# 7inch.net
KiCad netlist of a schematic drawn in Altium Designer
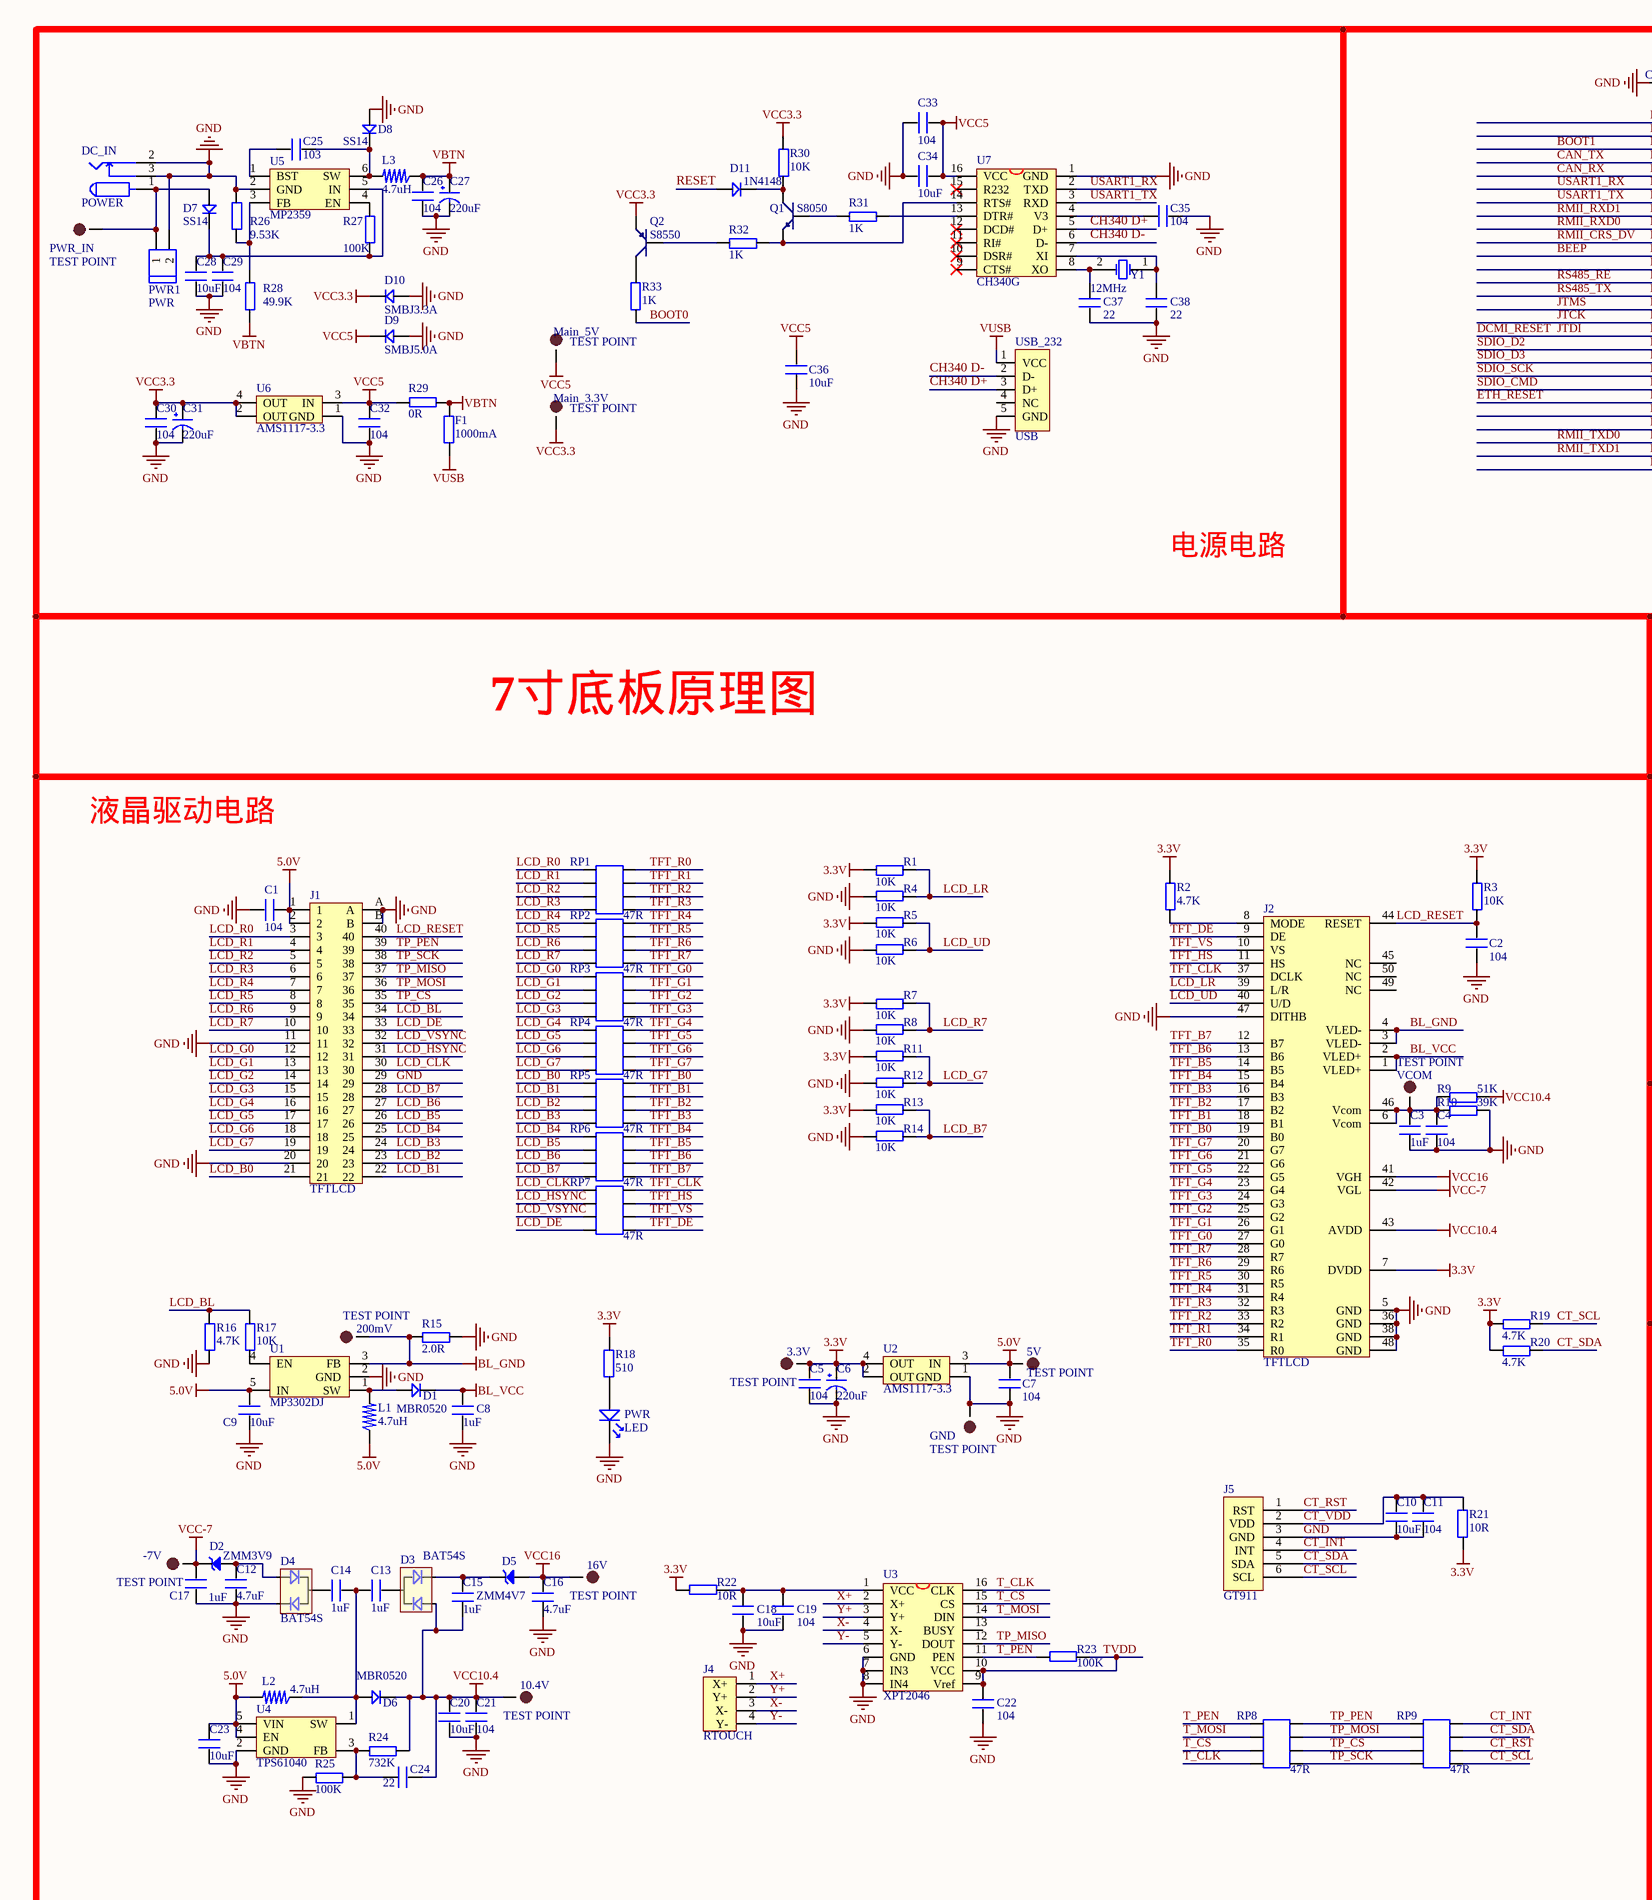
[diagram p0: 7inch底板原理图.SchDoc, left]
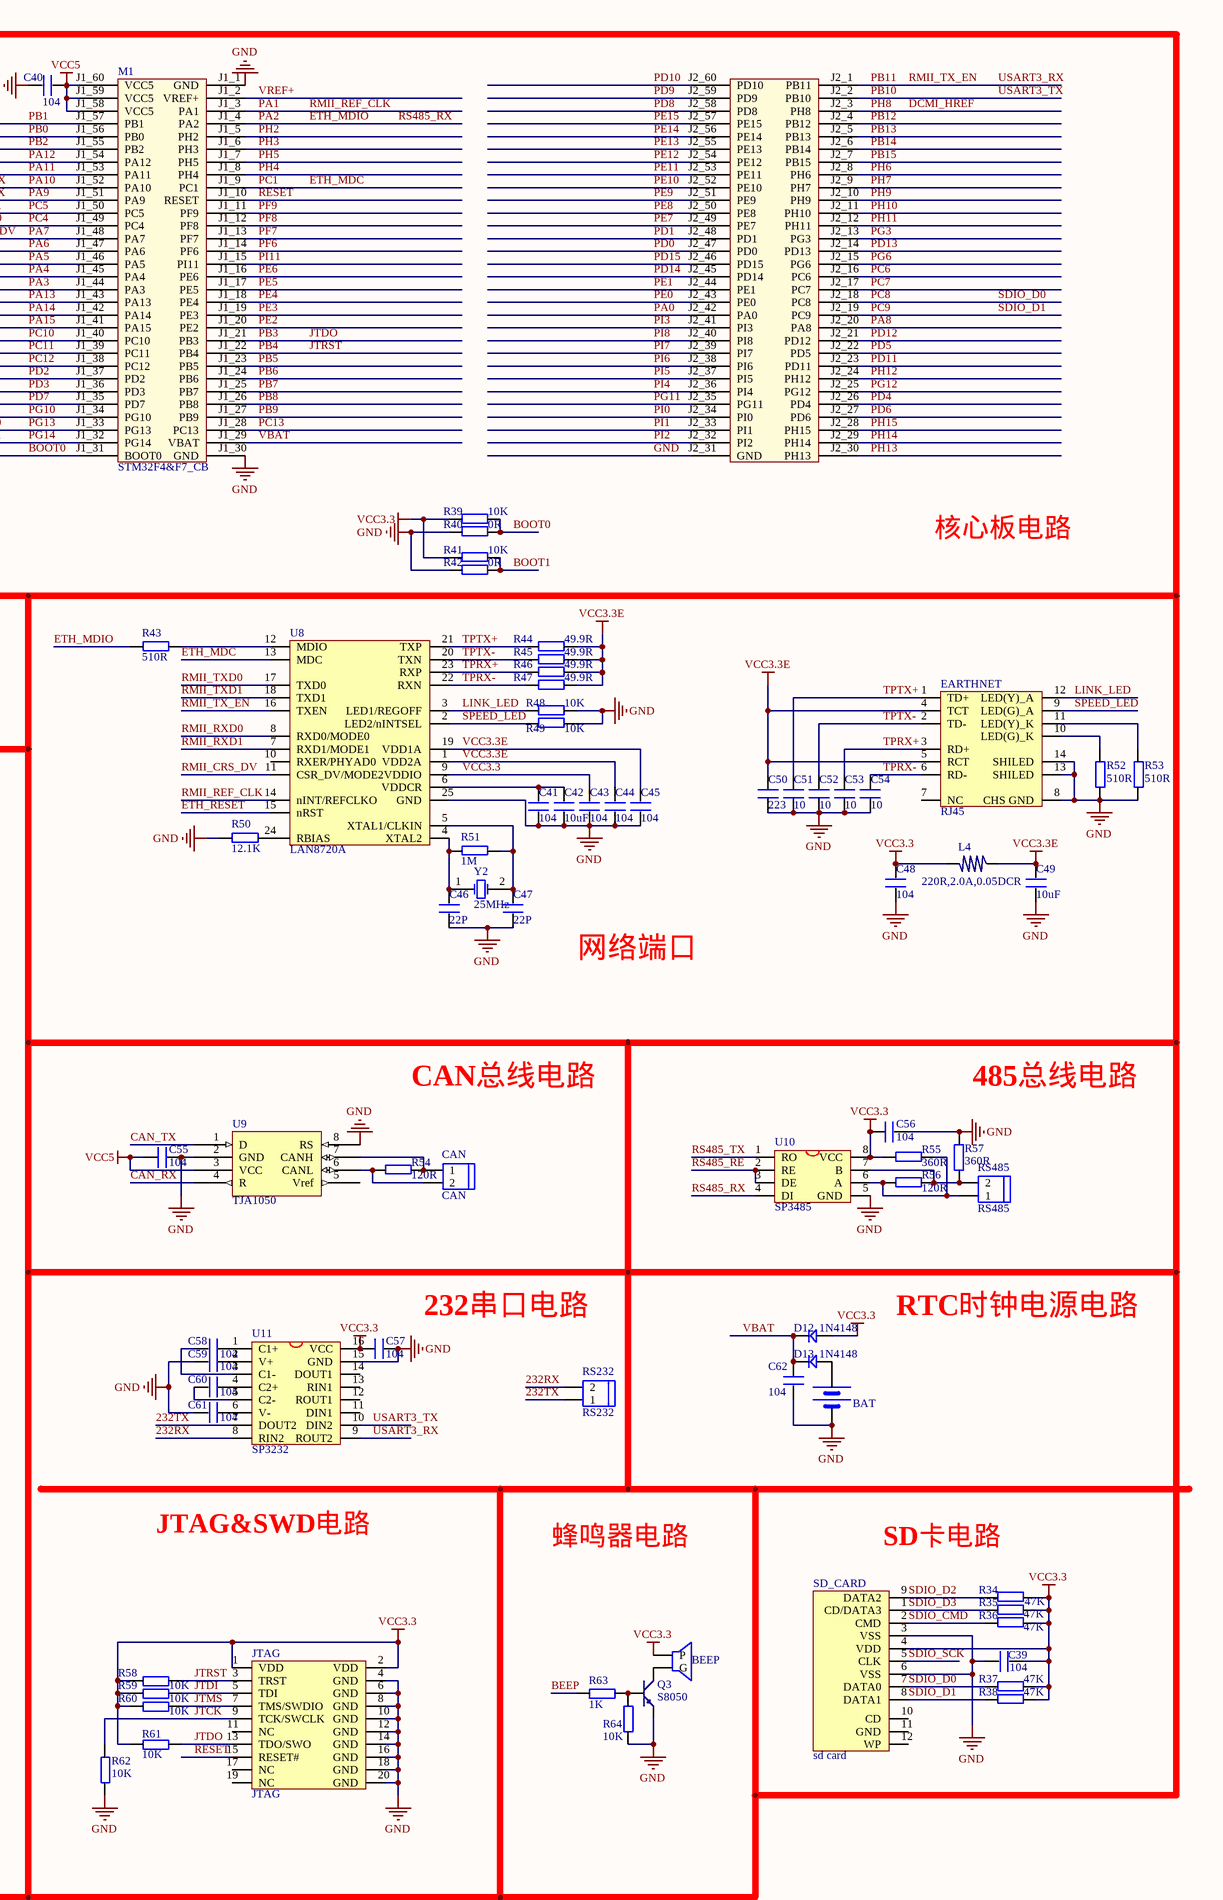
[diagram p1: 7inch底板原理图.SchDoc, right]

(export (version "E")
  (design (tool "Eeschema 10.0.6"))
  (components
    (comp (ref "-7V")
      (value "TEST POINT")
      (footprint "TP-1.5")
      (description "测试点")
      (libsource (lib "7寸RGB屏模块封装库") (part "TEST-POINT"))
    )
    (comp (ref "3.3V")
      (value "TEST POINT")
      (footprint "TP-1.5")
      (description "测试点")
      (libsource (lib "7寸RGB屏模块封装库") (part "TEST-POINT"))
    )
    (comp (ref "5V")
      (value "TEST POINT")
      (footprint "TP-1.5")
      (description "测试点")
      (libsource (lib "7寸RGB屏模块封装库") (part "TEST-POINT"))
    )
    (comp (ref "10.4V")
      (value "TEST POINT")
      (footprint "TP-1.5")
      (description "测试点")
      (libsource (lib "7寸RGB屏模块封装库") (part "TEST-POINT"))
    )
    (comp (ref "16V")
      (value "TEST POINT")
      (footprint "TP-1.5")
      (description "测试点")
      (libsource (lib "7寸RGB屏模块封装库") (part "TEST-POINT"))
    )
    (comp (ref "200mV")
      (value "TEST POINT")
      (footprint "TP-1.5")
      (description "测试点")
      (libsource (lib "7寸RGB屏模块封装库") (part "TEST-POINT"))
    )
    (comp (ref "BAT") (value "BATT") (footprint "BATM") (libsource (lib "底板封装库") (part "BAT")))
    (comp (ref "BEEP") (value "BEEP") (footprint "BELL-5") (libsource (lib "底板封装库") (part "BEEP")))
    (comp (ref "C1") (value "104") (footprint "0603P") (libsource (lib "7寸RGB屏模块封装库") (part "C")))
    (comp (ref "C2") (value "104") (footprint "0603P") (libsource (lib "7寸RGB屏模块封装库") (part "C")))
    (comp (ref "C3") (value "1uF") (footprint "0603P") (libsource (lib "7寸RGB屏模块封装库") (part "C")))
    (comp (ref "C4") (value "104") (footprint "0603P") (libsource (lib "7寸RGB屏模块封装库") (part "C")))
    (comp (ref "C5") (value "104") (footprint "0603P") (libsource (lib "7寸RGB屏模块封装库") (part "C")))
    (comp (ref "C6") (value "220uF") (footprint "CC6.56.5") (libsource (lib "7寸RGB屏模块封装库") (part "CAP")))
    (comp (ref "C7") (value "104") (footprint "0603P") (libsource (lib "7寸RGB屏模块封装库") (part "C")))
    (comp (ref "C8") (value "1uF") (footprint "0603P") (libsource (lib "7寸RGB屏模块封装库") (part "C")))
    (comp (ref "C9") (value "10uF") (footprint "0805") (libsource (lib "7寸RGB屏模块封装库") (part "C")))
    (comp (ref "C10") (value "10uF") (footprint "0805") (libsource (lib "7寸RGB屏模块封装库") (part "C")))
    (comp (ref "C11") (value "104") (footprint "0603P") (libsource (lib "7寸RGB屏模块封装库") (part "C")))
    (comp (ref "C12") (value "4.7uF") (footprint "0805") (libsource (lib "7寸RGB屏模块封装库") (part "C")))
    (comp (ref "C13") (value "1uF") (footprint "0603P") (libsource (lib "7寸RGB屏模块封装库") (part "C")))
    (comp (ref "C14") (value "1uF") (footprint "0603P") (libsource (lib "7寸RGB屏模块封装库") (part "C")))
    (comp (ref "C15") (value "1uF") (footprint "0603P") (libsource (lib "7寸RGB屏模块封装库") (part "C")))
    (comp (ref "C16") (value "4.7uF") (footprint "0805") (libsource (lib "7寸RGB屏模块封装库") (part "C")))
    (comp (ref "C17") (value "1uF") (footprint "0603P") (libsource (lib "7寸RGB屏模块封装库") (part "C")))
    (comp (ref "C18") (value "10uF") (footprint "0805") (libsource (lib "7寸RGB屏模块封装库") (part "C")))
    (comp (ref "C19") (value "104") (footprint "0603P") (libsource (lib "7寸RGB屏模块封装库") (part "C")))
    (comp (ref "C20") (value "10uF") (footprint "0805") (libsource (lib "7寸RGB屏模块封装库") (part "C")))
    (comp (ref "C21") (value "104") (footprint "0603P") (libsource (lib "7寸RGB屏模块封装库") (part "C")))
    (comp (ref "C22") (value "104") (footprint "0603P") (libsource (lib "7寸RGB屏模块封装库") (part "C")))
    (comp (ref "C23") (value "10uF") (footprint "0805") (libsource (lib "7寸RGB屏模块封装库") (part "C")))
    (comp (ref "C24") (value "22") (footprint "0603P") (libsource (lib "7寸RGB屏模块封装库") (part "C")))
    (comp (ref "C25") (value "103") (footprint "0603P") (libsource (lib "底板封装库") (part "C")))
    (comp (ref "C26") (value "104") (footprint "0603P") (libsource (lib "底板封装库") (part "C")))
    (comp (ref "C27") (value "220uF") (footprint "CC6.56.5") (libsource (lib "底板封装库") (part "CAP")))
    (comp (ref "C28") (value "10uF") (footprint "0805") (libsource (lib "底板封装库") (part "C")))
    (comp (ref "C29") (value "104") (footprint "0603P") (libsource (lib "底板封装库") (part "C")))
    (comp (ref "C30") (value "104") (footprint "0603P") (libsource (lib "底板封装库") (part "C")))
    (comp (ref "C31") (value "220uF") (footprint "CC6.56.5") (libsource (lib "底板封装库") (part "CAP")))
    (comp (ref "C32") (value "104") (footprint "0603P") (libsource (lib "底板封装库") (part "C")))
    (comp (ref "C33")
      (value "104")
      (footprint "0603P")
      (libsource (lib "altium-import") (part "root_0_mirrored_C_"))
    )
    (comp (ref "C34")
      (value "10uF")
      (footprint "0603P")
      (libsource (lib "altium-import") (part "root_0_mirrored_C_"))
    )
    (comp (ref "C35")
      (value "104")
      (footprint "0603P")
      (libsource (lib "altium-import") (part "root_0_mirrored_C_"))
    )
    (comp (ref "C36")
      (value "10uF")
      (footprint "0805")
      (libsource (lib "altium-import") (part "root_3_mirrored_C_"))
    )
    (comp (ref "C37")
      (value "22")
      (footprint "0603P")
      (libsource (lib "altium-import") (part "root_1_mirrored_C_"))
    )
    (comp (ref "C38")
      (value "22")
      (footprint "0603P")
      (libsource (lib "altium-import") (part "root_1_mirrored_C_"))
    )
    (comp (ref "C39")
      (value "104")
      (footprint "0603P")
      (libsource (lib "altium-import") (part "root_0_mirrored_C_"))
    )
    (comp (ref "C40")
      (value "104")
      (footprint "0603P")
      (libsource (lib "altium-import") (part "root_0_mirrored_C_"))
    )
    (comp (ref "C41") (value "104") (footprint "0603P") (libsource (lib "altium-import") (part "root_1_C_")))
    (comp (ref "C42") (value "10uF") (footprint "0805") (libsource (lib "altium-import") (part "root_1_C_")))
    (comp (ref "C43") (value "104") (footprint "0603P") (libsource (lib "altium-import") (part "root_1_C_")))
    (comp (ref "C44") (value "104") (footprint "0603P") (libsource (lib "altium-import") (part "root_1_C_")))
    (comp (ref "C45") (value "104") (footprint "0603P") (libsource (lib "altium-import") (part "root_1_C_")))
    (comp (ref "C46") (value "22P") (footprint "0603P") (libsource (lib "altium-import") (part "root_1_C_")))
    (comp (ref "C47") (value "22P") (footprint "0603P") (libsource (lib "altium-import") (part "root_1_C_")))
    (comp (ref "C48") (value "104") (footprint "0603P") (libsource (lib "altium-import") (part "root_1_C_")))
    (comp (ref "C49") (value "10uF") (footprint "0805") (libsource (lib "altium-import") (part "root_1_C_")))
    (comp (ref "C50") (value "223") (footprint "0603P") (libsource (lib "altium-import") (part "root_1_C_")))
    (comp (ref "C51") (value "10") (footprint "0603P") (libsource (lib "altium-import") (part "root_1_C_")))
    (comp (ref "C52") (value "10") (footprint "0603P") (libsource (lib "altium-import") (part "root_1_C_")))
    (comp (ref "C53") (value "10") (footprint "0603P") (libsource (lib "altium-import") (part "root_1_C_")))
    (comp (ref "C54") (value "10") (footprint "0603P") (libsource (lib "altium-import") (part "root_1_C_")))
    (comp (ref "C55") (value "104") (footprint "0603P") (libsource (lib "altium-import") (part "root_2_C_")))
    (comp (ref "C56") (value "104") (footprint "0603P") (libsource (lib "altium-import") (part "root_2_C_")))
    (comp (ref "C57") (value "104") (footprint "0603P") (libsource (lib "altium-import") (part "root_2_C_")))
    (comp (ref "C58") (value "104") (footprint "0603P") (libsource (lib "altium-import") (part "root_2_C_")))
    (comp (ref "C59") (value "104") (footprint "0603P") (libsource (lib "altium-import") (part "root_2_C_")))
    (comp (ref "C60") (value "104") (footprint "0603P") (libsource (lib "altium-import") (part "root_2_C_")))
    (comp (ref "C61") (value "104") (footprint "0603P") (libsource (lib "altium-import") (part "root_2_C_")))
    (comp (ref "C62") (value "104") (footprint "0603P") (libsource (lib "altium-import") (part "root_3_C_")))
    (comp (ref "CAN") (value "CAN") (footprint "HEAD2L-0.8") (libsource (lib "底板封装库") (part "HEAD2")))
    (comp (ref "D1")
      (value "MBR0520")
      (footprint "SOD-123")
      (description "1N4148")
      (libsource (lib "7寸RGB屏模块封装库") (part "D"))
    )
    (comp (ref "D2")
      (value "ZMM3V9")
      (footprint "DIODE_ZMMx")
      (description "ZMM3V6")
      (libsource (lib "7寸RGB屏模块封装库") (part "ZMM3V6"))
    )
    (comp (ref "D3")
      (value "BAT54S")
      (footprint "SOT-23")
      (description "双肖特基二极管")
      (libsource (lib "") (part "BAT54S_1"))
    )
    (comp (ref "D4")
      (value "BAT54S")
      (footprint "SOT-23")
      (description "双肖特基二极管")
      (libsource (lib "7寸RGB屏模块封装库") (part "BAT54S"))
    )
    (comp (ref "D5")
      (value "ZMM4V7")
      (footprint "DIODE_ZMMx")
      (description "ZMM3V6")
      (libsource (lib "7寸RGB屏模块封装库") (part "ZMM3V6"))
    )
    (comp (ref "D6")
      (value "MBR0520")
      (footprint "SOD-123")
      (description "1N4148")
      (libsource (lib "7寸RGB屏模块封装库") (part "D"))
    )
    (comp (ref "D7") (value "SS14") (footprint "DIODE_3*5.3") (libsource (lib "底板封装库") (part "D")))
    (comp (ref "D8") (value "SS14") (footprint "DIODE_3*5.3") (libsource (lib "底板封装库") (part "D")))
    (comp (ref "D9") (value "SMBJ5.0A") (footprint "SMBJ") (libsource (lib "阿波罗STM32F4&F7底板封装库") (part "D")))
    (comp (ref "D10") (value "SMBJ3.3A") (footprint "SMBJ") (libsource (lib "阿波罗STM32F4&F7底板封装库") (part "D")))
    (comp (ref "D11") (value "1N4148") (footprint "DIODE_SOP") (libsource (lib "底板封装库") (part "D")))
    (comp (ref "D12") (value "1N4148") (footprint "DIODE_SOP") (libsource (lib "底板封装库") (part "D")))
    (comp (ref "D13") (value "1N4148") (footprint "DIODE_SOP") (libsource (lib "底板封装库") (part "D")))
    (comp (ref "DC_IN") (value "POWER") (footprint "DC10B") (libsource (lib "底板封装库") (part "POW")))
    (comp (ref "EARTHNET")
      (value "RJ45")
      (footprint "HR911105A")
      (libsource (lib "ENC28J60网络模块封装库") (part "HR911105"))
    )
    (comp (ref "F1") (value "1000mA") (footprint "0805") (libsource (lib "底板封装库") (part "R")))
    (comp (ref "GND")
      (value "TEST POINT")
      (footprint "TP-1.5")
      (description "测试点")
      (libsource (lib "7寸RGB屏模块封装库") (part "TEST-POINT"))
    )
    (comp (ref "J1")
      (value "TFTLCD")
      (footprint "FPC-TOP40")
      (description "FPC-40P-0.5mm")
      (libsource (lib "7寸RGB屏模块封装库") (part "FPC-40"))
    )
    (comp (ref "J2")
      (value "TFTLCD")
      (footprint "FPC-TOP50")
      (description "7' TFTLCD")
      (libsource (lib "7寸RGB屏模块封装库") (part "AT070TN92"))
    )
    (comp (ref "J4")
      (value "RTOUCH")
      (footprint "FFC/SM1.0-4")
      (description "7' 电阻触摸屏")
      (libsource (lib "7寸RGB屏模块封装库") (part "RTOUCH"))
    )
    (comp (ref "J5")
      (value "GT911")
      (footprint "CTOUCH_6_BTM")
      (libsource (lib "7寸RGB屏模块封装库") (part "GT911"))
    )
    (comp (ref "JTAG") (value "JTAG") (footprint "JTAG_20") (libsource (lib "底板封装库") (part "JTAG")))
    (comp (ref "L1") (value "4.7uH") (footprint "L_CD43") (libsource (lib "") (part "L_SOP_1")))
    (comp (ref "L2") (value "4.7uH") (footprint "L_CD43") (libsource (lib "7寸RGB屏模块封装库") (part "L_SOP")))
    (comp (ref "L3") (value "4.7uH") (footprint "L_SOP74") (libsource (lib "7寸RGB屏模块封装库") (part "L_SOP")))
    (comp (ref "L4")
      (value "220R,2.0A,0.05DCR")
      (footprint "0603P")
      (libsource (lib "Explorer STM32F407封装库") (part "L"))
    )
    (comp (ref "M1")
      (value "STM32F4&F7_CB")
      (footprint "STM32F4&F7_CB")
      (description "F429/746 Core Board")
      (libsource (lib "底板封装库") (part "STM32F4&F7_CB"))
    )
    (comp (ref "Main_3.3V")
      (value "TEST POINT")
      (footprint "TP-1.5")
      (description "测试点")
      (libsource (lib "7寸RGB屏模块封装库") (part "TEST-POINT"))
    )
    (comp (ref "Main_5V")
      (value "TEST POINT")
      (footprint "TP-1.5")
      (description "测试点")
      (libsource (lib "7寸RGB屏模块封装库") (part "TEST-POINT"))
    )
    (comp (ref "PWR") (value "LED") (footprint "SMDLED") (libsource (lib "7寸RGB屏模块封装库") (part "LED")))
    (comp (ref "PWR1") (value "PWR") (footprint "HEAD2L-0.8") (libsource (lib "底板封装库") (part "HEAD2")))
    (comp (ref "PWR_IN")
      (value "TEST POINT")
      (footprint "TP-1.5")
      (description "测试点")
      (libsource (lib "7寸RGB屏模块封装库") (part "TEST-POINT"))
    )
    (comp (ref "Q1")
      (value "S8050")
      (footprint "SOT-23R")
      (description "8050/BCW846/BCW847")
      (libsource (lib "底板封装库") (part "NPN"))
    )
    (comp (ref "Q2")
      (value "S8550")
      (footprint "SOT-23R")
      (description "8550/BCW68")
      (libsource (lib "底板封装库") (part "PNP"))
    )
    (comp (ref "Q3")
      (value "S8050")
      (footprint "SOT-23R")
      (description "8050/BCW846/BCW847")
      (libsource (lib "底板封装库") (part "NPN"))
    )
    (comp (ref "R1") (value "10K") (footprint "0603P") (libsource (lib "7寸RGB屏模块封装库") (part "R")))
    (comp (ref "R2") (value "4.7K") (footprint "0603P") (libsource (lib "7寸RGB屏模块封装库") (part "R")))
    (comp (ref "R3") (value "10K") (footprint "0603P") (libsource (lib "7寸RGB屏模块封装库") (part "R")))
    (comp (ref "R4") (value "10K") (footprint "0603P") (libsource (lib "7寸RGB屏模块封装库") (part "R")))
    (comp (ref "R5") (value "10K") (footprint "0603P") (libsource (lib "7寸RGB屏模块封装库") (part "R")))
    (comp (ref "R6") (value "10K") (footprint "0603P") (libsource (lib "7寸RGB屏模块封装库") (part "R")))
    (comp (ref "R7") (value "10K") (footprint "0603P") (libsource (lib "7寸RGB屏模块封装库") (part "R")))
    (comp (ref "R8") (value "10K") (footprint "0603P") (libsource (lib "7寸RGB屏模块封装库") (part "R")))
    (comp (ref "R9") (value "51K") (footprint "0603P") (libsource (lib "7寸RGB屏模块封装库") (part "R")))
    (comp (ref "R10") (value "39K") (footprint "0603P") (libsource (lib "7寸RGB屏模块封装库") (part "R")))
    (comp (ref "R11") (value "10K") (footprint "0603P") (libsource (lib "7寸RGB屏模块封装库") (part "R")))
    (comp (ref "R12") (value "10K") (footprint "0603P") (libsource (lib "7寸RGB屏模块封装库") (part "R")))
    (comp (ref "R13") (value "10K") (footprint "0603P") (libsource (lib "7寸RGB屏模块封装库") (part "R")))
    (comp (ref "R14") (value "10K") (footprint "0603P") (libsource (lib "7寸RGB屏模块封装库") (part "R")))
    (comp (ref "R15") (value "2.0R") (footprint "0603P") (libsource (lib "7寸RGB屏模块封装库") (part "R")))
    (comp (ref "R16") (value "4.7K") (footprint "0603P") (libsource (lib "7寸RGB屏模块封装库") (part "R")))
    (comp (ref "R17") (value "10K") (footprint "0603P") (libsource (lib "7寸RGB屏模块封装库") (part "R")))
    (comp (ref "R18") (value "510") (footprint "0603P") (libsource (lib "7寸RGB屏模块封装库") (part "R")))
    (comp (ref "R19") (value "4.7K") (footprint "0603P") (libsource (lib "7寸RGB屏模块封装库") (part "R")))
    (comp (ref "R20") (value "4.7K") (footprint "0603P") (libsource (lib "7寸RGB屏模块封装库") (part "R")))
    (comp (ref "R21") (value "10R") (footprint "0603P") (libsource (lib "7寸RGB屏模块封装库") (part "R")))
    (comp (ref "R22") (value "10R") (footprint "0603P") (libsource (lib "7寸RGB屏模块封装库") (part "R")))
    (comp (ref "R23") (value "100K") (footprint "0603P") (libsource (lib "7寸RGB屏模块封装库") (part "R")))
    (comp (ref "R24") (value "732K") (footprint "0603P") (libsource (lib "7寸RGB屏模块封装库") (part "R")))
    (comp (ref "R25") (value "100K") (footprint "0603P") (libsource (lib "7寸RGB屏模块封装库") (part "R")))
    (comp (ref "R26") (value "9.53K") (footprint "0603P") (libsource (lib "底板封装库") (part "R")))
    (comp (ref "R27") (value "100K") (footprint "0603P") (libsource (lib "底板封装库") (part "R")))
    (comp (ref "R28") (value "49.9K") (footprint "0603P") (libsource (lib "底板封装库") (part "R")))
    (comp (ref "R29") (value "0R") (footprint "0805") (libsource (lib "底板封装库") (part "R")))
    (comp (ref "R30")
      (value "10K")
      (footprint "0603P")
      (libsource (lib "altium-import") (part "root_3_mirrored_R_"))
    )
    (comp (ref "R31")
      (value "1K")
      (footprint "0603P")
      (libsource (lib "altium-import") (part "root_0_mirrored_R_"))
    )
    (comp (ref "R32")
      (value "1K")
      (footprint "0603P")
      (libsource (lib "altium-import") (part "root_0_mirrored_R_"))
    )
    (comp (ref "R33") (value "1K") (footprint "0603P") (libsource (lib "altium-import") (part "root_3_R_")))
    (comp (ref "R34") (value "47K") (footprint "0603P") (libsource (lib "altium-import") (part "root_2_R_")))
    (comp (ref "R35") (value "47K") (footprint "0603P") (libsource (lib "altium-import") (part "root_2_R_")))
    (comp (ref "R36") (value "47K") (footprint "0603P") (libsource (lib "altium-import") (part "root_2_R_")))
    (comp (ref "R37") (value "47K") (footprint "0603P") (libsource (lib "altium-import") (part "root_2_R_")))
    (comp (ref "R38") (value "47K") (footprint "0603P") (libsource (lib "altium-import") (part "root_2_R_")))
    (comp (ref "R39") (value "10K") (footprint "0603P") (libsource (lib "altium-import") (part "root_2_R_")))
    (comp (ref "R40") (value "0R") (footprint "0603P") (libsource (lib "altium-import") (part "root_2_R_")))
    (comp (ref "R41") (value "10K") (footprint "0603P") (libsource (lib "altium-import") (part "root_2_R_")))
    (comp (ref "R42") (value "0R") (footprint "0603P") (libsource (lib "altium-import") (part "root_2_R_")))
    (comp (ref "R43") (value "510R") (footprint "0603P") (libsource (lib "altium-import") (part "root_2_R_")))
    (comp (ref "R44")
      (value "49.9R")
      (footprint "0603P")
      (libsource (lib "altium-import") (part "root_2_R_"))
    )
    (comp (ref "R45")
      (value "49.9R")
      (footprint "0603P")
      (libsource (lib "altium-import") (part "root_2_R_"))
    )
    (comp (ref "R46")
      (value "49.9R")
      (footprint "0603P")
      (libsource (lib "altium-import") (part "root_2_R_"))
    )
    (comp (ref "R47")
      (value "49.9R")
      (footprint "0603P")
      (libsource (lib "altium-import") (part "root_2_R_"))
    )
    (comp (ref "R48") (value "10K") (footprint "0603P") (libsource (lib "altium-import") (part "root_2_R_")))
    (comp (ref "R49") (value "10K") (footprint "0603P") (libsource (lib "altium-import") (part "root_2_R_")))
    (comp (ref "R50")
      (value "12.1K")
      (footprint "0603P")
      (libsource (lib "altium-import") (part "root_2_R_"))
    )
    (comp (ref "R51") (value "1M") (footprint "0603P") (libsource (lib "altium-import") (part "root_2_R_")))
    (comp (ref "R52") (value "510R") (footprint "0603P") (libsource (lib "altium-import") (part "root_1_R_")))
    (comp (ref "R53") (value "510R") (footprint "0603P") (libsource (lib "altium-import") (part "root_1_R_")))
    (comp (ref "R54") (value "120R") (footprint "0603P") (libsource (lib "altium-import") (part "root_2_R_")))
    (comp (ref "R55") (value "360R") (footprint "0603P") (libsource (lib "altium-import") (part "root_2_R_")))
    (comp (ref "R56") (value "120R") (footprint "0603P") (libsource (lib "altium-import") (part "root_2_R_")))
    (comp (ref "R57") (value "360R") (footprint "0603P") (libsource (lib "altium-import") (part "root_3_R_")))
    (comp (ref "R58") (value "10K") (footprint "0603P") (libsource (lib "altium-import") (part "root_0_R_")))
    (comp (ref "R59") (value "10K") (footprint "0603P") (libsource (lib "altium-import") (part "root_0_R_")))
    (comp (ref "R60") (value "10K") (footprint "0603P") (libsource (lib "altium-import") (part "root_0_R_")))
    (comp (ref "R61") (value "10K") (footprint "0603P") (libsource (lib "altium-import") (part "root_0_R_")))
    (comp (ref "R62") (value "10K") (footprint "0603P") (libsource (lib "altium-import") (part "root_1_R_")))
    (comp (ref "R63") (value "1K") (footprint "0603P") (libsource (lib "altium-import") (part "root_0_R_")))
    (comp (ref "R64") (value "10K") (footprint "0603P") (libsource (lib "altium-import") (part "root_1_R_")))
    (comp (ref "RP1")
      (value "47R")
      (footprint "8P4R_0603")
      (description "排阻")
      (libsource (lib "7寸RGB屏模块封装库") (part "R_PACK"))
    )
    (comp (ref "RP2")
      (value "47R")
      (footprint "8P4R_0603")
      (description "排阻")
      (libsource (lib "7寸RGB屏模块封装库") (part "R_PACK"))
    )
    (comp (ref "RP3")
      (value "47R")
      (footprint "8P4R_0603")
      (description "排阻")
      (libsource (lib "7寸RGB屏模块封装库") (part "R_PACK"))
    )
    (comp (ref "RP4")
      (value "47R")
      (footprint "8P4R_0603")
      (description "排阻")
      (libsource (lib "7寸RGB屏模块封装库") (part "R_PACK"))
    )
    (comp (ref "RP5")
      (value "47R")
      (footprint "8P4R_0603")
      (description "排阻")
      (libsource (lib "7寸RGB屏模块封装库") (part "R_PACK"))
    )
    (comp (ref "RP6")
      (value "47R")
      (footprint "8P4R_0603")
      (description "排阻")
      (libsource (lib "7寸RGB屏模块封装库") (part "R_PACK"))
    )
    (comp (ref "RP7")
      (value "47R")
      (footprint "8P4R_0603")
      (description "排阻")
      (libsource (lib "7寸RGB屏模块封装库") (part "R_PACK"))
    )
    (comp (ref "RP8")
      (value "47R")
      (footprint "8P4R_0603")
      (description "排阻")
      (libsource (lib "7寸RGB屏模块封装库") (part "R_PACK"))
    )
    (comp (ref "RP9")
      (value "47R")
      (footprint "8P4R_0603")
      (description "排阻")
      (libsource (lib "7寸RGB屏模块封装库") (part "R_PACK"))
    )
    (comp (ref "RS232") (value "RS232") (footprint "HEAD2L-0.8") (libsource (lib "底板封装库") (part "HEAD2")))
    (comp (ref "RS485") (value "RS485") (footprint "HEAD2L-0.8") (libsource (lib "底板封装库") (part "HEAD2")))
    (comp (ref "SD_CARD") (value "sd card") (footprint "SDCARD_L") (libsource (lib "底板封装库") (part "sd card")))
    (comp (ref "U1")
      (value "MP3302DJ")
      (footprint "SOT-23-5")
      (description "LCD背光IC")
      (libsource (lib "7寸RGB屏模块封装库") (part "MP3302"))
    )
    (comp (ref "U2")
      (value "AMS1117-3.3")
      (footprint "AMS1117")
      (libsource (lib "7寸RGB屏模块封装库") (part "AMS1117"))
    )
    (comp (ref "U3") (value "XPT2046") (footprint "SSOP16") (libsource (lib "7寸RGB屏模块封装库") (part "ADS7843")))
    (comp (ref "U4")
      (value "TPS61040")
      (footprint "SOT-23-5")
      (description "DC DC Step Up IC")
      (libsource (lib "7寸RGB屏模块封装库") (part "TPS61040"))
    )
    (comp (ref "U5")
      (value "MP2359")
      (footprint "SOT-23-6")
      (description "DC DC Step Down IC")
      (libsource (lib "底板封装库") (part "MP2359"))
    )
    (comp (ref "U6") (value "AMS1117-3.3") (footprint "AMS1117") (libsource (lib "底板封装库") (part "AMS1117")))
    (comp (ref "U7")
      (value "CH340G")
      (footprint "SOP16M")
      (description "USB2UART")
      (libsource (lib "底板封装库") (part "CH340G"))
    )
    (comp (ref "U8")
      (value "LAN8720A")
      (footprint "QFN24")
      (description "ETH PHY")
      (libsource (lib "底板封装库") (part "LAN8720"))
    )
    (comp (ref "U9") (value "TJA1050") (footprint "SOP-8") (libsource (lib "底板封装库") (part "SN65HVD230D")))
    (comp (ref "U10") (value "SP3485") (footprint "SOP-8") (libsource (lib "底板封装库") (part "MAX3485")))
    (comp (ref "U11") (value "SP3232") (footprint "SOP16M") (libsource (lib "底板封装库") (part "MAX3232")))
    (comp (ref "USB_232") (value "USB") (footprint "USB/SM0.8-6H5") (libsource (lib "底板封装库") (part "USB5")))
    (comp (ref "VCOM")
      (value "TEST POINT")
      (footprint "TP-1.5")
      (description "测试点")
      (libsource (lib "7寸RGB屏模块封装库") (part "TEST-POINT"))
    )
    (comp (ref "Y1")
      (value "12MHz")
      (footprint "XTAL_US")
      (description "Crystal Oscillator")
      (fields (field (name "PUBLISHER") "Altium Limited"))
      (libsource (lib "底板封装库") (part "XTAL"))
    )
    (comp (ref "Y2")
      (value "25MHz")
      (footprint "XTAL_US")
      (description "Crystal Oscillator")
      (fields (field (name "PUBLISHER") "Altium Limited"))
      (libsource (lib "Explorer STM32F407封装库") (part "XTAL"))
    )
  )
  (nets
    (net (code "1") (name "/232RX") (class "Default")
      (node (ref "RS232") (pin "2") (pinfunction "2_2") (pintype "passive"))
      (node (ref "U11") (pin "8") (pinfunction "RIN2_8") (pintype "passive"))
    )
    (net (code "2") (name "/232TX") (class "Default")
      (node (ref "RS232") (pin "1") (pinfunction "1_1") (pintype "passive"))
      (node (ref "U11") (pin "7") (pinfunction "DOUT2_7") (pintype "passive"))
    )
    (net (code "3") (name "/BEEP") (class "Default")
      (node (ref "M1") (pin "J1_47") (pinfunction "PA6_J1_47") (pintype "passive"))
      (node (ref "R63") (pin "1") (pintype "passive"))
    )
    (net (code "4") (name "/BOOT0") (class "Default")
      (node (ref "M1") (pin "J1_31") (pinfunction "BOOT0_J1_31") (pintype "passive"))
      (node (ref "R33") (pin "2") (pintype "passive"))
      (node (ref "R39") (pin "1") (pintype "passive"))
      (node (ref "R40") (pin "1") (pintype "passive"))
    )
    (net (code "5") (name "/BOOT1") (class "Default")
      (node (ref "M1") (pin "J1_55") (pinfunction "PB2_J1_55") (pintype "passive"))
      (node (ref "R41") (pin "1") (pintype "passive"))
      (node (ref "R42") (pin "1") (pintype "passive"))
    )
    (net (code "6") (name "/CAN_RX") (class "Default")
      (node (ref "M1") (pin "J1_53") (pinfunction "PA11_J1_53") (pintype "passive"))
      (node (ref "U9") (pin "4") (pinfunction "R_4") (pintype "output"))
    )
    (net (code "7") (name "/CAN_TX") (class "Default")
      (node (ref "M1") (pin "J1_54") (pinfunction "PA12_J1_54") (pintype "passive"))
      (node (ref "U9") (pin "1") (pinfunction "D_1") (pintype "input"))
    )
    (net (code "8") (name "/CH340 D+") (class "Default")
      (node (ref "U7") (pin "5") (pinfunction "D+_5") (pintype "passive"))
      (node (ref "USB_232") (pin "3") (pinfunction "D+_3") (pintype "passive"))
    )
    (net (code "9") (name "/CH340 D-") (class "Default")
      (node (ref "U7") (pin "6") (pinfunction "D-_6") (pintype "passive"))
      (node (ref "USB_232") (pin "2") (pinfunction "D-_2") (pintype "passive"))
    )
    (net (code "10") (name "/CT_INT") (class "Default")
      (node (ref "J5") (pin "4") (pinfunction "INT_4") (pintype "passive"))
      (node (ref "RP9") (pin "8") (pintype "passive"))
    )
    (net (code "11") (name "/CT_RST") (class "Default")
      (node (ref "J5") (pin "1") (pinfunction "RST_1") (pintype "passive"))
      (node (ref "RP9") (pin "4") (pintype "passive"))
    )
    (net (code "12") (name "/CT_SCL") (class "Default")
      (node (ref "J5") (pin "6") (pinfunction "SCL_6") (pintype "passive"))
      (node (ref "R19") (pin "2") (pintype "passive"))
      (node (ref "RP9") (pin "2") (pintype "passive"))
    )
    (net (code "13") (name "/CT_SDA") (class "Default")
      (node (ref "J5") (pin "5") (pinfunction "SDA_5") (pintype "passive"))
      (node (ref "R20") (pin "2") (pintype "passive"))
      (node (ref "RP9") (pin "6") (pintype "passive"))
    )
    (net (code "14") (name "/CT_VDD") (class "Default")
      (node (ref "C10") (pin "1") (pintype "passive"))
      (node (ref "C11") (pin "1") (pintype "passive"))
      (node (ref "J5") (pin "2") (pinfunction "VDD_2") (pintype "passive"))
      (node (ref "R21") (pin "2") (pintype "passive"))
    )
    (net (code "15") (name "/DCMI_HREF") (class "Default")
      (node (ref "M1") (pin "J2_3") (pinfunction "PH8_J2_3") (pintype "passive"))
    )
    (net (code "16") (name "/DCMI_RESET") (class "Default")
      (node (ref "JTAG") (pin "5") (pinfunction "TDI_5") (pintype "passive"))
      (node (ref "M1") (pin "J1_41") (pinfunction "PA15_J1_41") (pintype "passive"))
      (node (ref "R59") (pin "2") (pintype "passive"))
    )
    (net (code "17") (name "/ETH_MDC") (class "Default")
      (node (ref "M1") (pin "J1_9") (pinfunction "PC1_J1_9") (pintype "passive"))
      (node (ref "U8") (pin "13") (pinfunction "MDC_13") (pintype "passive"))
    )
    (net (code "18") (name "/ETH_MDIO") (class "Default")
      (node (ref "M1") (pin "J1_4") (pinfunction "PA2_J1_4") (pintype "passive"))
      (node (ref "R43") (pin "2") (pintype "passive"))
      (node (ref "U10") (pin "4") (pinfunction "DI_4") (pintype "passive"))
    )
    (net (code "19") (name "/ETH_RESET") (class "Default")
      (node (ref "M1") (pin "J1_36") (pinfunction "PD3_J1_36") (pintype "passive"))
      (node (ref "U8") (pin "15") (pinfunction "nRST_15") (pintype "passive"))
    )
    (net (code "20") (name "/JTCK") (class "Default")
      (node (ref "JTAG") (pin "9") (pinfunction "TCK/SWCLK_9") (pintype "passive"))
      (node (ref "M1") (pin "J1_42") (pinfunction "PA14_J1_42") (pintype "passive"))
      (node (ref "R62") (pin "2") (pintype "passive"))
    )
    (net (code "21") (name "/JTDO") (class "Default")
      (node (ref "JTAG") (pin "13") (pinfunction "TDO/SWO_13") (pintype "passive"))
      (node (ref "M1") (pin "J1_21") (pinfunction "PB3_J1_21") (pintype "passive"))
      (node (ref "R61") (pin "2") (pintype "passive"))
    )
    (net (code "22") (name "/JTMS") (class "Default")
      (node (ref "JTAG") (pin "7") (pinfunction "TMS/SWDIO_7") (pintype "passive"))
      (node (ref "M1") (pin "J1_43") (pinfunction "PA13_J1_43") (pintype "passive"))
      (node (ref "R60") (pin "2") (pintype "passive"))
    )
    (net (code "23") (name "/JTRST") (class "Default")
      (node (ref "JTAG") (pin "3") (pinfunction "TRST_3") (pintype "passive"))
      (node (ref "M1") (pin "J1_22") (pinfunction "PB4_J1_22") (pintype "passive"))
      (node (ref "R58") (pin "2") (pintype "passive"))
    )
    (net (code "24") (name "/LCD_B0") (class "Default")
      (node (ref "J1") (pin "21") (pinfunction "21_21") (pintype "passive"))
      (node (ref "RP5") (pin "2") (pintype "passive"))
    )
    (net (code "25") (name "/LCD_B1") (class "Default")
      (node (ref "J1") (pin "22") (pinfunction "22_22") (pintype "passive"))
      (node (ref "RP5") (pin "4") (pintype "passive"))
    )
    (net (code "26") (name "/LCD_B2") (class "Default")
      (node (ref "J1") (pin "23") (pinfunction "23_23") (pintype "passive"))
      (node (ref "RP5") (pin "6") (pintype "passive"))
    )
    (net (code "27") (name "/LCD_B3") (class "Default")
      (node (ref "J1") (pin "24") (pinfunction "24_24") (pintype "passive"))
      (node (ref "RP5") (pin "8") (pintype "passive"))
    )
    (net (code "28") (name "/LCD_B4") (class "Default")
      (node (ref "J1") (pin "25") (pinfunction "25_25") (pintype "passive"))
      (node (ref "RP6") (pin "2") (pintype "passive"))
    )
    (net (code "29") (name "/LCD_B5") (class "Default")
      (node (ref "J1") (pin "26") (pinfunction "26_26") (pintype "passive"))
      (node (ref "RP6") (pin "4") (pintype "passive"))
    )
    (net (code "30") (name "/LCD_B6") (class "Default")
      (node (ref "J1") (pin "27") (pinfunction "27_27") (pintype "passive"))
      (node (ref "RP6") (pin "6") (pintype "passive"))
    )
    (net (code "31") (name "/LCD_B7") (class "Default")
      (node (ref "J1") (pin "28") (pinfunction "28_28") (pintype "passive"))
      (node (ref "R13") (pin "1") (pintype "passive"))
      (node (ref "R14") (pin "1") (pintype "passive"))
      (node (ref "RP6") (pin "8") (pintype "passive"))
    )
    (net (code "32") (name "/LCD_BL") (class "Default")
      (node (ref "J1") (pin "34") (pinfunction "34_34") (pintype "passive"))
      (node (ref "R16") (pin "2") (pintype "passive"))
      (node (ref "R17") (pin "2") (pintype "passive"))
    )
    (net (code "33") (name "/LCD_CLK") (class "Default")
      (node (ref "J1") (pin "30") (pinfunction "30_30") (pintype "passive"))
      (node (ref "RP7") (pin "2") (pintype "passive"))
    )
    (net (code "34") (name "/LCD_DE") (class "Default")
      (node (ref "J1") (pin "33") (pinfunction "33_33") (pintype "passive"))
      (node (ref "RP7") (pin "8") (pintype "passive"))
    )
    (net (code "35") (name "/LCD_G0") (class "Default")
      (node (ref "J1") (pin "12") (pinfunction "12_12") (pintype "passive"))
      (node (ref "RP3") (pin "2") (pintype "passive"))
    )
    (net (code "36") (name "/LCD_G1") (class "Default")
      (node (ref "J1") (pin "13") (pinfunction "13_13") (pintype "passive"))
      (node (ref "RP3") (pin "4") (pintype "passive"))
    )
    (net (code "37") (name "/LCD_G2") (class "Default")
      (node (ref "J1") (pin "14") (pinfunction "14_14") (pintype "passive"))
      (node (ref "RP3") (pin "6") (pintype "passive"))
    )
    (net (code "38") (name "/LCD_G3") (class "Default")
      (node (ref "J1") (pin "15") (pinfunction "15_15") (pintype "passive"))
      (node (ref "RP3") (pin "8") (pintype "passive"))
    )
    (net (code "39") (name "/LCD_G4") (class "Default")
      (node (ref "J1") (pin "16") (pinfunction "16_16") (pintype "passive"))
      (node (ref "RP4") (pin "2") (pintype "passive"))
    )
    (net (code "40") (name "/LCD_G5") (class "Default")
      (node (ref "J1") (pin "17") (pinfunction "17_17") (pintype "passive"))
      (node (ref "RP4") (pin "4") (pintype "passive"))
    )
    (net (code "41") (name "/LCD_G6") (class "Default")
      (node (ref "J1") (pin "18") (pinfunction "18_18") (pintype "passive"))
      (node (ref "RP4") (pin "6") (pintype "passive"))
    )
    (net (code "42") (name "/LCD_G7") (class "Default")
      (node (ref "J1") (pin "19") (pinfunction "19_19") (pintype "passive"))
      (node (ref "R11") (pin "1") (pintype "passive"))
      (node (ref "R12") (pin "1") (pintype "passive"))
      (node (ref "RP4") (pin "8") (pintype "passive"))
    )
    (net (code "43") (name "/LCD_HSYNC") (class "Default")
      (node (ref "J1") (pin "31") (pinfunction "31_31") (pintype "passive"))
      (node (ref "RP7") (pin "4") (pintype "passive"))
    )
    (net (code "44") (name "/LCD_LR") (class "Default")
      (node (ref "J2") (pin "39") (pinfunction "L/R_39") (pintype "passive"))
      (node (ref "R1") (pin "2") (pintype "passive"))
      (node (ref "R4") (pin "1") (pintype "passive"))
    )
    (net (code "45") (name "/LCD_R0") (class "Default")
      (node (ref "J1") (pin "3") (pinfunction "3_3") (pintype "passive"))
      (node (ref "RP1") (pin "2") (pintype "passive"))
    )
    (net (code "46") (name "/LCD_R1") (class "Default")
      (node (ref "J1") (pin "4") (pinfunction "4_4") (pintype "passive"))
      (node (ref "RP1") (pin "4") (pintype "passive"))
    )
    (net (code "47") (name "/LCD_R2") (class "Default")
      (node (ref "J1") (pin "5") (pinfunction "5_5") (pintype "passive"))
      (node (ref "RP1") (pin "6") (pintype "passive"))
    )
    (net (code "48") (name "/LCD_R3") (class "Default")
      (node (ref "J1") (pin "6") (pinfunction "6_6") (pintype "passive"))
      (node (ref "RP1") (pin "8") (pintype "passive"))
    )
    (net (code "49") (name "/LCD_R4") (class "Default")
      (node (ref "J1") (pin "7") (pinfunction "7_7") (pintype "passive"))
      (node (ref "RP2") (pin "2") (pintype "passive"))
    )
    (net (code "50") (name "/LCD_R5") (class "Default")
      (node (ref "J1") (pin "8") (pinfunction "8_8") (pintype "passive"))
      (node (ref "RP2") (pin "4") (pintype "passive"))
    )
    (net (code "51") (name "/LCD_R6") (class "Default")
      (node (ref "J1") (pin "9") (pinfunction "9_9") (pintype "passive"))
      (node (ref "RP2") (pin "6") (pintype "passive"))
    )
    (net (code "52") (name "/LCD_R7") (class "Default")
      (node (ref "J1") (pin "10") (pinfunction "10_10") (pintype "passive"))
      (node (ref "R7") (pin "2") (pintype "passive"))
      (node (ref "R8") (pin "1") (pintype "passive"))
      (node (ref "RP2") (pin "8") (pintype "passive"))
    )
    (net (code "53") (name "/LCD_RESET") (class "Default")
      (node (ref "C2") (pin "2") (pintype "passive"))
      (node (ref "J1") (pin "40") (pinfunction "40_40") (pintype "passive"))
      (node (ref "J2") (pin "44") (pinfunction "RESET_44") (pintype "passive"))
      (node (ref "R3") (pin "1") (pintype "passive"))
    )
    (net (code "54") (name "/LCD_UD") (class "Default")
      (node (ref "J2") (pin "40") (pinfunction "U/D_40") (pintype "passive"))
      (node (ref "R5") (pin "1") (pintype "passive"))
      (node (ref "R6") (pin "1") (pintype "passive"))
    )
    (net (code "55") (name "/LCD_VSYNC") (class "Default")
      (node (ref "J1") (pin "32") (pinfunction "32_32") (pintype "passive"))
      (node (ref "RP7") (pin "6") (pintype "passive"))
    )
    (net (code "56") (name "/LINK_LED") (class "Default")
      (node (ref "EARTHNET") (pin "12") (pinfunction "LED(Y)_A_12") (pintype "passive"))
      (node (ref "R48") (pin "2") (pintype "passive"))
      (node (ref "U8") (pin "3") (pinfunction "LED1/REGOFF_3") (pintype "passive"))
    )
    (net (code "57") (name "/PA0") (class "Default")
      (node (ref "M1") (pin "J2_42") (pinfunction "PA0_J2_42") (pintype "passive"))
    )
    (net (code "58") (name "/PA1") (class "Default")
      (node (ref "M1") (pin "J1_3") (pinfunction "PA1_J1_3") (pintype "passive"))
      (node (ref "U8") (pin "14") (pinfunction "nINT/REFCLKO_14") (pintype "passive"))
    )
    (net (code "59") (name "/PA3") (class "Default")
      (node (ref "M1") (pin "J1_44") (pinfunction "PA3_J1_44") (pintype "passive"))
      (node (ref "U10") (pin "1") (pinfunction "RO_1") (pintype "passive"))
    )
    (net (code "60") (name "/PA4") (class "Default")
      (node (ref "M1") (pin "J1_45") (pinfunction "PA4_J1_45") (pintype "passive"))
      (node (ref "U10") (pin "2") (pinfunction "RE_2") (pintype "passive"))
      (node (ref "U10") (pin "3") (pinfunction "DE_3") (pintype "passive"))
    )
    (net (code "61") (name "/PA5") (class "Default")
      (node (ref "M1") (pin "J1_46") (pinfunction "PA5_J1_46") (pintype "passive"))
    )
    (net (code "62") (name "/PA7") (class "Default")
      (node (ref "M1") (pin "J1_48") (pinfunction "PA7_J1_48") (pintype "passive"))
      (node (ref "U8") (pin "11") (pinfunction "CSR_DV/MODE2_11") (pintype "passive"))
    )
    (net (code "63") (name "/PA8") (class "Default")
      (node (ref "M1") (pin "J2_20") (pinfunction "PA8_J2_20") (pintype "passive"))
    )
    (net (code "64") (name "/PA9") (class "Default")
      (node (ref "M1") (pin "J1_51") (pinfunction "PA9_J1_51") (pintype "passive"))
      (node (ref "U7") (pin "3") (pinfunction "RXD_3") (pintype "passive"))
    )
    (net (code "65") (name "/PA10") (class "Default")
      (node (ref "M1") (pin "J1_52") (pinfunction "PA10_J1_52") (pintype "passive"))
      (node (ref "U7") (pin "2") (pinfunction "TXD_2") (pintype "passive"))
    )
    (net (code "66") (name "/PB0") (class "Default")
      (node (ref "M1") (pin "J1_56") (pinfunction "PB0_J1_56") (pintype "passive"))
    )
    (net (code "67") (name "/PB1") (class "Default")
      (node (ref "M1") (pin "J1_57") (pinfunction "PB1_J1_57") (pintype "passive"))
    )
    (net (code "68") (name "/PB5") (class "Default")
      (node (ref "M1") (pin "J1_23") (pinfunction "PB5_J1_23") (pintype "passive"))
    )
    (net (code "69") (name "/PB6") (class "Default")
      (node (ref "M1") (pin "J1_24") (pinfunction "PB6_J1_24") (pintype "passive"))
    )
    (net (code "70") (name "/PB7") (class "Default")
      (node (ref "M1") (pin "J1_25") (pinfunction "PB7_J1_25") (pintype "passive"))
    )
    (net (code "71") (name "/PB8") (class "Default")
      (node (ref "M1") (pin "J1_26") (pinfunction "PB8_J1_26") (pintype "passive"))
    )
    (net (code "72") (name "/PB9") (class "Default")
      (node (ref "M1") (pin "J1_27") (pinfunction "PB9_J1_27") (pintype "passive"))
    )
    (net (code "73") (name "/PB10") (class "Default")
      (node (ref "M1") (pin "J2_2") (pinfunction "PB10_J2_2") (pintype "passive"))
      (node (ref "U11") (pin "10") (pinfunction "DIN2_10") (pintype "passive"))
    )
    (net (code "74") (name "/PB11") (class "Default")
      (node (ref "M1") (pin "J2_1") (pinfunction "PB11_J2_1") (pintype "passive"))
      (node (ref "U11") (pin "9") (pinfunction "ROUT2_9") (pintype "passive"))
      (node (ref "U8") (pin "16") (pinfunction "TXEN_16") (pintype "passive"))
    )
    (net (code "75") (name "/PB12") (class "Default")
      (node (ref "M1") (pin "J2_4") (pinfunction "PB12_J2_4") (pintype "passive"))
    )
    (net (code "76") (name "/PB13") (class "Default")
      (node (ref "M1") (pin "J2_5") (pinfunction "PB13_J2_5") (pintype "passive"))
    )
    (net (code "77") (name "/PB14") (class "Default")
      (node (ref "M1") (pin "J2_6") (pinfunction "PB14_J2_6") (pintype "passive"))
    )
    (net (code "78") (name "/PB15") (class "Default")
      (node (ref "M1") (pin "J2_7") (pinfunction "PB15_J2_7") (pintype "passive"))
    )
    (net (code "79") (name "/PC4") (class "Default")
      (node (ref "M1") (pin "J1_49") (pinfunction "PC4_J1_49") (pintype "passive"))
      (node (ref "U8") (pin "8") (pinfunction "RXD0/MODE0_8") (pintype "passive"))
    )
    (net (code "80") (name "/PC5") (class "Default")
      (node (ref "M1") (pin "J1_50") (pinfunction "PC5_J1_50") (pintype "passive"))
      (node (ref "U8") (pin "7") (pinfunction "RXD1/MODE1_7") (pintype "passive"))
    )
    (net (code "81") (name "/PC6") (class "Default")
      (node (ref "M1") (pin "J2_16") (pinfunction "PC6_J2_16") (pintype "passive"))
    )
    (net (code "82") (name "/PC7") (class "Default")
      (node (ref "M1") (pin "J2_17") (pinfunction "PC7_J2_17") (pintype "passive"))
    )
    (net (code "83") (name "/PC8") (class "Default")
      (node (ref "M1") (pin "J2_18") (pinfunction "PC8_J2_18") (pintype "passive"))
      (node (ref "R37") (pin "2") (pintype "passive"))
      (node (ref "SD_CARD") (pin "7") (pinfunction "DATA0_7") (pintype "passive"))
    )
    (net (code "84") (name "/PC9") (class "Default")
      (node (ref "M1") (pin "J2_19") (pinfunction "PC9_J2_19") (pintype "passive"))
      (node (ref "R38") (pin "2") (pintype "passive"))
      (node (ref "SD_CARD") (pin "8") (pinfunction "DATA1_8") (pintype "passive"))
    )
    (net (code "85") (name "/PC10") (class "Default")
      (node (ref "M1") (pin "J1_40") (pinfunction "PC10_J1_40") (pintype "passive"))
      (node (ref "R34") (pin "2") (pintype "passive"))
      (node (ref "SD_CARD") (pin "9") (pinfunction "DATA2_9") (pintype "passive"))
    )
    (net (code "86") (name "/PC11") (class "Default")
      (node (ref "M1") (pin "J1_39") (pinfunction "PC11_J1_39") (pintype "passive"))
      (node (ref "R35") (pin "2") (pintype "passive"))
      (node (ref "SD_CARD") (pin "1") (pinfunction "CD/DATA3_1") (pintype "passive"))
    )
    (net (code "87") (name "/PC12") (class "Default")
      (node (ref "M1") (pin "J1_38") (pinfunction "PC12_J1_38") (pintype "passive"))
      (node (ref "SD_CARD") (pin "5") (pinfunction "CLK_5") (pintype "passive"))
    )
    (net (code "88") (name "/PC13") (class "Default")
      (node (ref "M1") (pin "J1_28") (pinfunction "PC13_J1_28") (pintype "passive"))
    )
    (net (code "89") (name "/PD0") (class "Default")
      (node (ref "M1") (pin "J2_47") (pinfunction "PD0_J2_47") (pintype "passive"))
    )
    (net (code "90") (name "/PD1") (class "Default")
      (node (ref "M1") (pin "J2_48") (pinfunction "PD1_J2_48") (pintype "passive"))
    )
    (net (code "91") (name "/PD2") (class "Default")
      (node (ref "M1") (pin "J1_37") (pinfunction "PD2_J1_37") (pintype "passive"))
      (node (ref "R36") (pin "2") (pintype "passive"))
      (node (ref "SD_CARD") (pin "2") (pinfunction "CMD_2") (pintype "passive"))
    )
    (net (code "92") (name "/PD4") (class "Default")
      (node (ref "M1") (pin "J2_26") (pinfunction "PD4_J2_26") (pintype "passive"))
    )
    (net (code "93") (name "/PD5") (class "Default")
      (node (ref "M1") (pin "J2_22") (pinfunction "PD5_J2_22") (pintype "passive"))
    )
    (net (code "94") (name "/PD6") (class "Default")
      (node (ref "M1") (pin "J2_27") (pinfunction "PD6_J2_27") (pintype "passive"))
    )
    (net (code "95") (name "/PD7") (class "Default")
      (node (ref "M1") (pin "J1_35") (pinfunction "PD7_J1_35") (pintype "passive"))
    )
    (net (code "96") (name "/PD8") (class "Default")
      (node (ref "M1") (pin "J2_58") (pinfunction "PD8_J2_58") (pintype "passive"))
    )
    (net (code "97") (name "/PD9") (class "Default")
      (node (ref "M1") (pin "J2_59") (pinfunction "PD9_J2_59") (pintype "passive"))
    )
    (net (code "98") (name "/PD10") (class "Default")
      (node (ref "M1") (pin "J2_60") (pinfunction "PD10_J2_60") (pintype "passive"))
    )
    (net (code "99") (name "/PD11") (class "Default")
      (node (ref "M1") (pin "J2_23") (pinfunction "PD11_J2_23") (pintype "passive"))
    )
    (net (code "100") (name "/PD12") (class "Default")
      (node (ref "M1") (pin "J2_21") (pinfunction "PD12_J2_21") (pintype "passive"))
    )
    (net (code "101") (name "/PD13") (class "Default")
      (node (ref "M1") (pin "J2_14") (pinfunction "PD13_J2_14") (pintype "passive"))
    )
    (net (code "102") (name "/PD14") (class "Default")
      (node (ref "M1") (pin "J2_45") (pinfunction "PD14_J2_45") (pintype "passive"))
    )
    (net (code "103") (name "/PD15") (class "Default")
      (node (ref "M1") (pin "J2_46") (pinfunction "PD15_J2_46") (pintype "passive"))
    )
    (net (code "104") (name "/PE0") (class "Default")
      (node (ref "M1") (pin "J2_43") (pinfunction "PE0_J2_43") (pintype "passive"))
    )
    (net (code "105") (name "/PE1") (class "Default")
      (node (ref "M1") (pin "J2_44") (pinfunction "PE1_J2_44") (pintype "passive"))
    )
    (net (code "106") (name "/PE2") (class "Default")
      (node (ref "M1") (pin "J1_20") (pinfunction "PE2_J1_20") (pintype "passive"))
    )
    (net (code "107") (name "/PE3") (class "Default")
      (node (ref "M1") (pin "J1_19") (pinfunction "PE3_J1_19") (pintype "passive"))
    )
    (net (code "108") (name "/PE4") (class "Default")
      (node (ref "M1") (pin "J1_18") (pinfunction "PE4_J1_18") (pintype "passive"))
    )
    (net (code "109") (name "/PE5") (class "Default")
      (node (ref "M1") (pin "J1_17") (pinfunction "PE5_J1_17") (pintype "passive"))
    )
    (net (code "110") (name "/PE6") (class "Default")
      (node (ref "M1") (pin "J1_16") (pinfunction "PE6_J1_16") (pintype "passive"))
    )
    (net (code "111") (name "/PE7") (class "Default")
      (node (ref "M1") (pin "J2_49") (pinfunction "PE7_J2_49") (pintype "passive"))
    )
    (net (code "112") (name "/PE8") (class "Default")
      (node (ref "M1") (pin "J2_50") (pinfunction "PE8_J2_50") (pintype "passive"))
    )
    (net (code "113") (name "/PE9") (class "Default")
      (node (ref "M1") (pin "J2_51") (pinfunction "PE9_J2_51") (pintype "passive"))
    )
    (net (code "114") (name "/PE10") (class "Default")
      (node (ref "M1") (pin "J2_52") (pinfunction "PE10_J2_52") (pintype "passive"))
    )
    (net (code "115") (name "/PE11") (class "Default")
      (node (ref "M1") (pin "J2_53") (pinfunction "PE11_J2_53") (pintype "passive"))
    )
    (net (code "116") (name "/PE12") (class "Default")
      (node (ref "M1") (pin "J2_54") (pinfunction "PE12_J2_54") (pintype "passive"))
    )
    (net (code "117") (name "/PE13") (class "Default")
      (node (ref "M1") (pin "J2_55") (pinfunction "PE13_J2_55") (pintype "passive"))
    )
    (net (code "118") (name "/PE14") (class "Default")
      (node (ref "M1") (pin "J2_56") (pinfunction "PE14_J2_56") (pintype "passive"))
    )
    (net (code "119") (name "/PE15") (class "Default")
      (node (ref "M1") (pin "J2_57") (pinfunction "PE15_J2_57") (pintype "passive"))
    )
    (net (code "120") (name "/PF6") (class "Default")
      (node (ref "M1") (pin "J1_14") (pinfunction "PF6_J1_14") (pintype "passive"))
    )
    (net (code "121") (name "/PF7") (class "Default")
      (node (ref "M1") (pin "J1_13") (pinfunction "PF7_J1_13") (pintype "passive"))
    )
    (net (code "122") (name "/PF8") (class "Default")
      (node (ref "M1") (pin "J1_12") (pinfunction "PF8_J1_12") (pintype "passive"))
    )
    (net (code "123") (name "/PF9") (class "Default")
      (node (ref "M1") (pin "J1_11") (pinfunction "PF9_J1_11") (pintype "passive"))
    )
    (net (code "124") (name "/PG3") (class "Default")
      (node (ref "M1") (pin "J2_13") (pinfunction "PG3_J2_13") (pintype "passive"))
    )
    (net (code "125") (name "/PG6") (class "Default")
      (node (ref "M1") (pin "J2_15") (pinfunction "PG6_J2_15") (pintype "passive"))
    )
    (net (code "126") (name "/PG10") (class "Default")
      (node (ref "M1") (pin "J1_34") (pinfunction "PG10_J1_34") (pintype "passive"))
    )
    (net (code "127") (name "/PG11") (class "Default")
      (node (ref "M1") (pin "J2_35") (pinfunction "PG11_J2_35") (pintype "passive"))
    )
    (net (code "128") (name "/PG12") (class "Default")
      (node (ref "M1") (pin "J2_25") (pinfunction "PG12_J2_25") (pintype "passive"))
    )
    (net (code "129") (name "/PG13") (class "Default")
      (node (ref "M1") (pin "J1_33") (pinfunction "PG13_J1_33") (pintype "passive"))
      (node (ref "U8") (pin "17") (pinfunction "TXD0_17") (pintype "passive"))
    )
    (net (code "130") (name "/PG14") (class "Default")
      (node (ref "M1") (pin "J1_32") (pinfunction "PG14_J1_32") (pintype "passive"))
      (node (ref "U8") (pin "18") (pinfunction "TXD1_18") (pintype "passive"))
    )
    (net (code "131") (name "/PH2") (class "Default")
      (node (ref "M1") (pin "J1_5") (pinfunction "PH2_J1_5") (pintype "passive"))
    )
    (net (code "132") (name "/PH3") (class "Default")
      (node (ref "M1") (pin "J1_6") (pinfunction "PH3_J1_6") (pintype "passive"))
    )
    (net (code "133") (name "/PH4") (class "Default")
      (node (ref "M1") (pin "J1_8") (pinfunction "PH4_J1_8") (pintype "passive"))
    )
    (net (code "134") (name "/PH5") (class "Default")
      (node (ref "M1") (pin "J1_7") (pinfunction "PH5_J1_7") (pintype "passive"))
    )
    (net (code "135") (name "/PH6") (class "Default")
      (node (ref "M1") (pin "J2_8") (pinfunction "PH6_J2_8") (pintype "passive"))
    )
    (net (code "136") (name "/PH7") (class "Default")
      (node (ref "M1") (pin "J2_9") (pinfunction "PH7_J2_9") (pintype "passive"))
    )
    (net (code "137") (name "/PH9") (class "Default")
      (node (ref "M1") (pin "J2_10") (pinfunction "PH9_J2_10") (pintype "passive"))
    )
    (net (code "138") (name "/PH10") (class "Default")
      (node (ref "M1") (pin "J2_11") (pinfunction "PH10_J2_11") (pintype "passive"))
    )
    (net (code "139") (name "/PH11") (class "Default")
      (node (ref "M1") (pin "J2_12") (pinfunction "PH11_J2_12") (pintype "passive"))
    )
    (net (code "140") (name "/PH12") (class "Default")
      (node (ref "M1") (pin "J2_24") (pinfunction "PH12_J2_24") (pintype "passive"))
    )
    (net (code "141") (name "/PH13") (class "Default")
      (node (ref "M1") (pin "J2_30") (pinfunction "PH13_J2_30") (pintype "passive"))
    )
    (net (code "142") (name "/PH14") (class "Default")
      (node (ref "M1") (pin "J2_29") (pinfunction "PH14_J2_29") (pintype "passive"))
    )
    (net (code "143") (name "/PH15") (class "Default")
      (node (ref "M1") (pin "J2_28") (pinfunction "PH15_J2_28") (pintype "passive"))
    )
    (net (code "144") (name "/PI0") (class "Default")
      (node (ref "M1") (pin "J2_34") (pinfunction "PI0_J2_34") (pintype "passive"))
    )
    (net (code "145") (name "/PI1") (class "Default")
      (node (ref "M1") (pin "J2_33") (pinfunction "PI1_J2_33") (pintype "passive"))
    )
    (net (code "146") (name "/PI2") (class "Default")
      (node (ref "M1") (pin "J2_32") (pinfunction "PI2_J2_32") (pintype "passive"))
    )
    (net (code "147") (name "/PI3") (class "Default")
      (node (ref "M1") (pin "J2_41") (pinfunction "PI3_J2_41") (pintype "passive"))
    )
    (net (code "148") (name "/PI4") (class "Default")
      (node (ref "M1") (pin "J2_36") (pinfunction "PI4_J2_36") (pintype "passive"))
    )
    (net (code "149") (name "/PI5") (class "Default")
      (node (ref "M1") (pin "J2_37") (pinfunction "PI5_J2_37") (pintype "passive"))
    )
    (net (code "150") (name "/PI6") (class "Default")
      (node (ref "M1") (pin "J2_38") (pinfunction "PI6_J2_38") (pintype "passive"))
    )
    (net (code "151") (name "/PI7") (class "Default")
      (node (ref "M1") (pin "J2_39") (pinfunction "PI7_J2_39") (pintype "passive"))
    )
    (net (code "152") (name "/PI8") (class "Default")
      (node (ref "M1") (pin "J2_40") (pinfunction "PI8_J2_40") (pintype "passive"))
    )
    (net (code "153") (name "/PI11") (class "Default")
      (node (ref "M1") (pin "J1_15") (pinfunction "PI11_J1_15") (pintype "passive"))
    )
    (net (code "154") (name "/RESET") (class "Default")
      (node (ref "D11") (pin "1") (pintype "passive"))
      (node (ref "JTAG") (pin "15") (pinfunction "RESET#_15") (pintype "passive"))
      (node (ref "M1") (pin "J1_10") (pinfunction "RESET_J1_10") (pintype "passive"))
    )
    (net (code "155") (name "/SPEED_LED") (class "Default")
      (node (ref "EARTHNET") (pin "9") (pinfunction "LED(G)_A_9") (pintype "passive"))
      (node (ref "R49") (pin "2") (pintype "passive"))
      (node (ref "U8") (pin "2") (pinfunction "LED2/nINTSEL_2") (pintype "passive"))
    )
    (net (code "156") (name "/TFT_B0") (class "Default")
      (node (ref "J2") (pin "19") (pinfunction "B0_19") (pintype "passive"))
      (node (ref "RP5") (pin "1") (pintype "passive"))
    )
    (net (code "157") (name "/TFT_B1") (class "Default")
      (node (ref "J2") (pin "18") (pinfunction "B1_18") (pintype "passive"))
      (node (ref "RP5") (pin "3") (pintype "passive"))
    )
    (net (code "158") (name "/TFT_B2") (class "Default")
      (node (ref "J2") (pin "17") (pinfunction "B2_17") (pintype "passive"))
      (node (ref "RP5") (pin "5") (pintype "passive"))
    )
    (net (code "159") (name "/TFT_B3") (class "Default")
      (node (ref "J2") (pin "16") (pinfunction "B3_16") (pintype "passive"))
      (node (ref "RP5") (pin "7") (pintype "passive"))
    )
    (net (code "160") (name "/TFT_B4") (class "Default")
      (node (ref "J2") (pin "15") (pinfunction "B4_15") (pintype "passive"))
      (node (ref "RP6") (pin "1") (pintype "passive"))
    )
    (net (code "161") (name "/TFT_B5") (class "Default")
      (node (ref "J2") (pin "14") (pinfunction "B5_14") (pintype "passive"))
      (node (ref "RP6") (pin "3") (pintype "passive"))
    )
    (net (code "162") (name "/TFT_B6") (class "Default")
      (node (ref "J2") (pin "13") (pinfunction "B6_13") (pintype "passive"))
      (node (ref "RP6") (pin "5") (pintype "passive"))
    )
    (net (code "163") (name "/TFT_B7") (class "Default")
      (node (ref "J2") (pin "12") (pinfunction "B7_12") (pintype "passive"))
      (node (ref "RP6") (pin "7") (pintype "passive"))
    )
    (net (code "164") (name "/TFT_CLK") (class "Default")
      (node (ref "J2") (pin "37") (pinfunction "DCLK_37") (pintype "passive"))
      (node (ref "RP7") (pin "1") (pintype "passive"))
    )
    (net (code "165") (name "/TFT_DE") (class "Default")
      (node (ref "J2") (pin "9") (pinfunction "DE_9") (pintype "passive"))
      (node (ref "RP7") (pin "7") (pintype "passive"))
    )
    (net (code "166") (name "/TFT_G0") (class "Default")
      (node (ref "J2") (pin "27") (pinfunction "G0_27") (pintype "passive"))
      (node (ref "RP3") (pin "1") (pintype "passive"))
    )
    (net (code "167") (name "/TFT_G1") (class "Default")
      (node (ref "J2") (pin "26") (pinfunction "G1_26") (pintype "passive"))
      (node (ref "RP3") (pin "3") (pintype "passive"))
    )
    (net (code "168") (name "/TFT_G2") (class "Default")
      (node (ref "J2") (pin "25") (pinfunction "G2_25") (pintype "passive"))
      (node (ref "RP3") (pin "5") (pintype "passive"))
    )
    (net (code "169") (name "/TFT_G3") (class "Default")
      (node (ref "J2") (pin "24") (pinfunction "G3_24") (pintype "passive"))
      (node (ref "RP3") (pin "7") (pintype "passive"))
    )
    (net (code "170") (name "/TFT_G4") (class "Default")
      (node (ref "J2") (pin "23") (pinfunction "G4_23") (pintype "passive"))
      (node (ref "RP4") (pin "1") (pintype "passive"))
    )
    (net (code "171") (name "/TFT_G5") (class "Default")
      (node (ref "J2") (pin "22") (pinfunction "G5_22") (pintype "passive"))
      (node (ref "RP4") (pin "3") (pintype "passive"))
    )
    (net (code "172") (name "/TFT_G6") (class "Default")
      (node (ref "J2") (pin "21") (pinfunction "G6_21") (pintype "passive"))
      (node (ref "RP4") (pin "5") (pintype "passive"))
    )
    (net (code "173") (name "/TFT_G7") (class "Default")
      (node (ref "J2") (pin "20") (pinfunction "G7_20") (pintype "passive"))
      (node (ref "RP4") (pin "7") (pintype "passive"))
    )
    (net (code "174") (name "/TFT_HS") (class "Default")
      (node (ref "J2") (pin "11") (pinfunction "HS_11") (pintype "passive"))
      (node (ref "RP7") (pin "3") (pintype "passive"))
    )
    (net (code "175") (name "/TFT_R0") (class "Default")
      (node (ref "J2") (pin "35") (pinfunction "R0_35") (pintype "passive"))
      (node (ref "RP1") (pin "1") (pintype "passive"))
    )
    (net (code "176") (name "/TFT_R1") (class "Default")
      (node (ref "J2") (pin "34") (pinfunction "R1_34") (pintype "passive"))
      (node (ref "RP1") (pin "3") (pintype "passive"))
    )
    (net (code "177") (name "/TFT_R2") (class "Default")
      (node (ref "J2") (pin "33") (pinfunction "R2_33") (pintype "passive"))
      (node (ref "RP1") (pin "5") (pintype "passive"))
    )
    (net (code "178") (name "/TFT_R3") (class "Default")
      (node (ref "J2") (pin "32") (pinfunction "R3_32") (pintype "passive"))
      (node (ref "RP1") (pin "7") (pintype "passive"))
    )
    (net (code "179") (name "/TFT_R4") (class "Default")
      (node (ref "J2") (pin "31") (pinfunction "R4_31") (pintype "passive"))
      (node (ref "RP2") (pin "1") (pintype "passive"))
    )
    (net (code "180") (name "/TFT_R5") (class "Default")
      (node (ref "J2") (pin "30") (pinfunction "R5_30") (pintype "passive"))
      (node (ref "RP2") (pin "3") (pintype "passive"))
    )
    (net (code "181") (name "/TFT_R6") (class "Default")
      (node (ref "J2") (pin "29") (pinfunction "R6_29") (pintype "passive"))
      (node (ref "RP2") (pin "5") (pintype "passive"))
    )
    (net (code "182") (name "/TFT_R7") (class "Default")
      (node (ref "J2") (pin "28") (pinfunction "R7_28") (pintype "passive"))
      (node (ref "RP2") (pin "7") (pintype "passive"))
    )
    (net (code "183") (name "/TFT_VS") (class "Default")
      (node (ref "J2") (pin "10") (pinfunction "VS_10") (pintype "passive"))
      (node (ref "RP7") (pin "5") (pintype "passive"))
    )
    (net (code "184") (name "/TPRX+") (class "Default")
      (node (ref "C53") (pin "2") (pintype "passive"))
      (node (ref "EARTHNET") (pin "3") (pinfunction "RD+_3") (pintype "passive"))
      (node (ref "R46") (pin "2") (pintype "passive"))
      (node (ref "U8") (pin "23") (pinfunction "RXP_23") (pintype "passive"))
    )
    (net (code "185") (name "/TPRX-") (class "Default")
      (node (ref "C54") (pin "2") (pintype "passive"))
      (node (ref "EARTHNET") (pin "6") (pinfunction "RD-_6") (pintype "passive"))
      (node (ref "R47") (pin "2") (pintype "passive"))
      (node (ref "U8") (pin "22") (pinfunction "RXN_22") (pintype "passive"))
    )
    (net (code "186") (name "/TPTX+") (class "Default")
      (node (ref "C51") (pin "2") (pintype "passive"))
      (node (ref "EARTHNET") (pin "1") (pinfunction "TD+_1") (pintype "passive"))
      (node (ref "R44") (pin "2") (pintype "passive"))
      (node (ref "U8") (pin "21") (pinfunction "TXP_21") (pintype "passive"))
    )
    (net (code "187") (name "/TPTX-") (class "Default")
      (node (ref "C52") (pin "2") (pintype "passive"))
      (node (ref "EARTHNET") (pin "2") (pinfunction "TD-_2") (pintype "passive"))
      (node (ref "R45") (pin "2") (pintype "passive"))
      (node (ref "U8") (pin "20") (pinfunction "TXN_20") (pintype "passive"))
    )
    (net (code "188") (name "/TP_CS") (class "Default")
      (node (ref "J1") (pin "35") (pinfunction "35_35") (pintype "passive"))
      (node (ref "RP8") (pin "4") (pintype "passive"))
      (node (ref "RP9") (pin "3") (pintype "passive"))
    )
    (net (code "189") (name "/TP_MISO") (class "Default")
      (node (ref "J1") (pin "37") (pinfunction "37_37") (pintype "passive"))
      (node (ref "U3") (pin "12") (pinfunction "DOUT_12") (pintype "passive"))
    )
    (net (code "190") (name "/TP_MOSI") (class "Default")
      (node (ref "J1") (pin "36") (pinfunction "36_36") (pintype "passive"))
      (node (ref "RP8") (pin "6") (pintype "passive"))
      (node (ref "RP9") (pin "5") (pintype "passive"))
    )
    (net (code "191") (name "/TP_PEN") (class "Default")
      (node (ref "J1") (pin "39") (pinfunction "39_39") (pintype "passive"))
      (node (ref "RP8") (pin "8") (pintype "passive"))
      (node (ref "RP9") (pin "7") (pintype "passive"))
    )
    (net (code "192") (name "/TP_SCK") (class "Default")
      (node (ref "J1") (pin "38") (pinfunction "38_38") (pintype "passive"))
      (node (ref "RP8") (pin "2") (pintype "passive"))
      (node (ref "RP9") (pin "1") (pintype "passive"))
    )
    (net (code "193") (name "/TVDD") (class "Default")
      (node (ref "C22") (pin "2") (pintype "passive"))
      (node (ref "R23") (pin "1") (pintype "passive"))
      (node (ref "U3") (pin "10") (pinfunction "VCC_10") (pintype "passive"))
      (node (ref "U3") (pin "9") (pinfunction "Vref_9") (pintype "passive"))
    )
    (net (code "194") (name "/T_CLK") (class "Default")
      (node (ref "RP8") (pin "1") (pintype "passive"))
      (node (ref "U3") (pin "16") (pinfunction "CLK_16") (pintype "passive"))
    )
    (net (code "195") (name "/T_CS") (class "Default")
      (node (ref "RP8") (pin "3") (pintype "passive"))
      (node (ref "U3") (pin "15") (pinfunction "CS_15") (pintype "passive"))
    )
    (net (code "196") (name "/T_MOSI") (class "Default")
      (node (ref "RP8") (pin "5") (pintype "passive"))
      (node (ref "U3") (pin "14") (pinfunction "DIN_14") (pintype "passive"))
    )
    (net (code "197") (name "/T_PEN") (class "Default")
      (node (ref "R23") (pin "2") (pintype "passive"))
      (node (ref "RP8") (pin "7") (pintype "passive"))
      (node (ref "U3") (pin "11") (pinfunction "PEN_11") (pintype "passive"))
    )
    (net (code "198") (name "/VBAT") (class "Default")
      (node (ref "C62") (pin "1") (pintype "passive"))
      (node (ref "D12") (pin "2") (pintype "passive"))
      (node (ref "D13") (pin "2") (pintype "passive"))
      (node (ref "M1") (pin "J1_29") (pinfunction "VBAT_J1_29") (pintype "passive"))
    )
    (net (code "199") (name "/VREF+") (class "Default")
      (node (ref "M1") (pin "J1_2") (pinfunction "VREF+_J1_2") (pintype "passive"))
    )
    (net (code "200") (name "/X+") (class "Default")
      (node (ref "J4") (pin "1") (pinfunction "X+_1") (pintype "passive"))
      (node (ref "U3") (pin "2") (pinfunction "X+_2") (pintype "passive"))
    )
    (net (code "201") (name "/X-") (class "Default")
      (node (ref "J4") (pin "3") (pinfunction "X-_3") (pintype "passive"))
      (node (ref "U3") (pin "4") (pinfunction "X-_4") (pintype "passive"))
    )
    (net (code "202") (name "/Y+") (class "Default")
      (node (ref "J4") (pin "2") (pinfunction "Y+_2") (pintype "passive"))
      (node (ref "U3") (pin "3") (pinfunction "Y+_3") (pintype "passive"))
    )
    (net (code "203") (name "/Y-") (class "Default")
      (node (ref "J4") (pin "4") (pinfunction "Y-_4") (pintype "passive"))
      (node (ref "U3") (pin "5") (pinfunction "Y-_5") (pintype "passive"))
    )
    (net (code "204") (name "3.3V") (class "Default")
      (node (ref "3.3V") (pin "1") (pinfunction "1_1") (pintype "passive"))
      (node (ref "C5") (pin "2") (pintype "passive"))
      (node (ref "C6") (pin "1") (pinfunction "VCC_1") (pintype "passive"))
      (node (ref "J2") (pin "7") (pinfunction "DVDD_7") (pintype "passive"))
      (node (ref "R1") (pin "1") (pintype "passive"))
      (node (ref "R11") (pin "2") (pintype "passive"))
      (node (ref "R13") (pin "2") (pintype "passive"))
      (node (ref "R18") (pin "1") (pintype "passive"))
      (node (ref "R19") (pin "1") (pintype "passive"))
      (node (ref "R2") (pin "2") (pintype "passive"))
      (node (ref "R20") (pin "1") (pintype "passive"))
      (node (ref "R21") (pin "1") (pintype "passive"))
      (node (ref "R22") (pin "2") (pintype "passive"))
      (node (ref "R3") (pin "2") (pintype "passive"))
      (node (ref "R5") (pin "2") (pintype "passive"))
      (node (ref "R7") (pin "1") (pintype "passive"))
      (node (ref "U2") (pin "2") (pinfunction "OUT_2") (pintype "passive"))
      (node (ref "U2") (pin "4") (pinfunction "OUT_4") (pintype "passive"))
    )
    (net (code "205") (name "5.0V") (class "Default")
      (node (ref "5V") (pin "1") (pinfunction "1_1") (pintype "passive"))
      (node (ref "C1") (pin "2") (pintype "passive"))
      (node (ref "C23") (pin "2") (pintype "passive"))
      (node (ref "C7") (pin "2") (pintype "passive"))
      (node (ref "C9") (pin "2") (pintype "passive"))
      (node (ref "J1") (pin "1") (pinfunction "1_1") (pintype "passive"))
      (node (ref "J1") (pin "2") (pinfunction "2_2") (pintype "passive"))
      (node (ref "L1") (pin "1") (pinfunction "1_1") (pintype "passive"))
      (node (ref "L2") (pin "2") (pinfunction "2_2") (pintype "passive"))
      (node (ref "U1") (pin "5") (pinfunction "IN_5") (pintype "passive"))
      (node (ref "U2") (pin "3") (pinfunction "IN_3") (pintype "passive"))
      (node (ref "U4") (pin "4") (pinfunction "EN_4") (pintype "passive"))
      (node (ref "U4") (pin "5") (pinfunction "VIN_5") (pintype "passive"))
    )
    (net (code "206") (name "BL_GND") (class "Default")
      (node (ref "200mV") (pin "1") (pinfunction "1_1") (pintype "passive"))
      (node (ref "J2") (pin "3") (pinfunction "VLED-_3") (pintype "passive"))
      (node (ref "J2") (pin "4") (pinfunction "VLED-_4") (pintype "passive"))
      (node (ref "R15") (pin "1") (pintype "passive"))
      (node (ref "U1") (pin "3") (pinfunction "FB_3") (pintype "passive"))
    )
    (net (code "207") (name "BL_VCC") (class "Default")
      (node (ref "C8") (pin "2") (pintype "passive"))
      (node (ref "D1") (pin "2") (pintype "passive"))
      (node (ref "J2") (pin "1") (pinfunction "VLED+_1") (pintype "passive"))
      (node (ref "J2") (pin "2") (pinfunction "VLED+_2") (pintype "passive"))
    )
    (net (code "208") (name "GND") (class "Default")
      (node (ref "BAT") (pin "2") (pinfunction "GND_2") (pintype "passive"))
      (node (ref "C1") (pin "1") (pintype "passive"))
      (node (ref "C10") (pin "2") (pintype "passive"))
      (node (ref "C11") (pin "2") (pintype "passive"))
      (node (ref "C12") (pin "2") (pintype "passive"))
      (node (ref "C16") (pin "2") (pintype "passive"))
      (node (ref "C17") (pin "2") (pintype "passive"))
      (node (ref "C18") (pin "1") (pintype "passive"))
      (node (ref "C19") (pin "1") (pintype "passive"))
      (node (ref "C2") (pin "1") (pintype "passive"))
      (node (ref "C20") (pin "1") (pintype "passive"))
      (node (ref "C21") (pin "1") (pintype "passive"))
      (node (ref "C22") (pin "1") (pintype "passive"))
      (node (ref "C23") (pin "1") (pintype "passive"))
      (node (ref "C26") (pin "1") (pintype "passive"))
      (node (ref "C27") (pin "2") (pinfunction "GND_2") (pintype "passive"))
      (node (ref "C28") (pin "1") (pintype "passive"))
      (node (ref "C29") (pin "1") (pintype "passive"))
      (node (ref "C3") (pin "1") (pintype "passive"))
      (node (ref "C30") (pin "1") (pintype "passive"))
      (node (ref "C31") (pin "2") (pinfunction "GND_2") (pintype "passive"))
      (node (ref "C32") (pin "1") (pintype "passive"))
      (node (ref "C33") (pin "2") (pintype "passive"))
      (node (ref "C34") (pin "2") (pintype "passive"))
      (node (ref "C35") (pin "1") (pintype "passive"))
      (node (ref "C36") (pin "2") (pintype "passive"))
      (node (ref "C37") (pin "1") (pintype "passive"))
      (node (ref "C38") (pin "1") (pintype "passive"))
      (node (ref "C39") (pin "2") (pintype "passive"))
      (node (ref "C4") (pin "1") (pintype "passive"))
      (node (ref "C40") (pin "2") (pintype "passive"))
      (node (ref "C41") (pin "1") (pintype "passive"))
      (node (ref "C42") (pin "1") (pintype "passive"))
      (node (ref "C43") (pin "1") (pintype "passive"))
      (node (ref "C44") (pin "1") (pintype "passive"))
      (node (ref "C45") (pin "1") (pintype "passive"))
      (node (ref "C46") (pin "1") (pintype "passive"))
      (node (ref "C47") (pin "1") (pintype "passive"))
      (node (ref "C48") (pin "1") (pintype "passive"))
      (node (ref "C49") (pin "1") (pintype "passive"))
      (node (ref "C5") (pin "1") (pintype "passive"))
      (node (ref "C50") (pin "1") (pintype "passive"))
      (node (ref "C51") (pin "1") (pintype "passive"))
      (node (ref "C52") (pin "1") (pintype "passive"))
      (node (ref "C53") (pin "1") (pintype "passive"))
      (node (ref "C54") (pin "1") (pintype "passive"))
      (node (ref "C55") (pin "1") (pintype "passive"))
      (node (ref "C56") (pin "1") (pintype "passive"))
      (node (ref "C57") (pin "1") (pintype "passive"))
      (node (ref "C59") (pin "2") (pintype "passive"))
      (node (ref "C6") (pin "2") (pinfunction "GND_2") (pintype "passive"))
      (node (ref "C61") (pin "2") (pintype "passive"))
      (node (ref "C62") (pin "2") (pintype "passive"))
      (node (ref "C7") (pin "1") (pintype "passive"))
      (node (ref "C8") (pin "1") (pintype "passive"))
      (node (ref "C9") (pin "1") (pintype "passive"))
      (node (ref "D10") (pin "1") (pintype "passive"))
      (node (ref "D4") (pin "2") (pintype "passive"))
      (node (ref "D8") (pin "1") (pintype "passive"))
      (node (ref "D9") (pin "1") (pintype "passive"))
      (node (ref "DC_IN") (pin "2") (pintype "passive"))
      (node (ref "DC_IN") (pin "3") (pintype "passive"))
      (node (ref "EARTHNET") (pin "13") (pinfunction "SHILED_13") (pintype "passive"))
      (node (ref "EARTHNET") (pin "14") (pinfunction "SHILED_14") (pintype "passive"))
      (node (ref "EARTHNET") (pin "8") (pinfunction "CHS_GND_8") (pintype "passive"))
      (node (ref "GND") (pin "1") (pinfunction "1_1") (pintype "passive"))
      (node (ref "J1") (pin "11") (pinfunction "11_11") (pintype "passive"))
      (node (ref "J1") (pin "20") (pinfunction "20_20") (pintype "passive"))
      (node (ref "J1") (pin "29") (pinfunction "29_29") (pintype "passive"))
      (node (ref "J1") (pin "A") (pinfunction "A_A") (pintype "passive"))
      (node (ref "J1") (pin "B") (pinfunction "B_B") (pintype "passive"))
      (node (ref "J2") (pin "36") (pinfunction "GND_36") (pintype "passive"))
      (node (ref "J2") (pin "38") (pinfunction "GND_38") (pintype "passive"))
      (node (ref "J2") (pin "47") (pinfunction "DITHB_47") (pintype "passive"))
      (node (ref "J2") (pin "48") (pinfunction "GND_48") (pintype "passive"))
      (node (ref "J2") (pin "5") (pinfunction "GND_5") (pintype "passive"))
      (node (ref "J5") (pin "3") (pinfunction "GND_3") (pintype "passive"))
      (node (ref "JTAG") (pin "10") (pinfunction "GND_10") (pintype "passive"))
      (node (ref "JTAG") (pin "12") (pinfunction "GND_12") (pintype "passive"))
      (node (ref "JTAG") (pin "14") (pinfunction "GND_14") (pintype "passive"))
      (node (ref "JTAG") (pin "16") (pinfunction "GND_16") (pintype "passive"))
      (node (ref "JTAG") (pin "18") (pinfunction "GND_18") (pintype "passive"))
      (node (ref "JTAG") (pin "20") (pinfunction "GND_20") (pintype "passive"))
      (node (ref "JTAG") (pin "4") (pinfunction "GND_4") (pintype "passive"))
      (node (ref "JTAG") (pin "6") (pinfunction "GND_6") (pintype "passive"))
      (node (ref "JTAG") (pin "8") (pinfunction "GND_8") (pintype "passive"))
      (node (ref "M1") (pin "J1_1") (pinfunction "GND_J1_1") (pintype "passive"))
      (node (ref "M1") (pin "J1_30") (pinfunction "GND_J1_30") (pintype "passive"))
      (node (ref "M1") (pin "J2_31") (pinfunction "GND_J2_31") (pintype "passive"))
      (node (ref "PWR") (pin "2") (pinfunction "2_2") (pintype "passive"))
      (node (ref "PWR1") (pin "2") (pinfunction "2_2") (pintype "passive"))
      (node (ref "Q3") (pin "1") (pinfunction "E_1") (pintype "passive"))
      (node (ref "R10") (pin "2") (pintype "passive"))
      (node (ref "R12") (pin "2") (pintype "passive"))
      (node (ref "R14") (pin "2") (pintype "passive"))
      (node (ref "R15") (pin "2") (pintype "passive"))
      (node (ref "R16") (pin "1") (pintype "passive"))
      (node (ref "R25") (pin "1") (pintype "passive"))
      (node (ref "R26") (pin "2") (pintype "passive"))
      (node (ref "R4") (pin "2") (pintype "passive"))
      (node (ref "R40") (pin "2") (pintype "passive"))
      (node (ref "R42") (pin "2") (pintype "passive"))
      (node (ref "R48") (pin "1") (pintype "passive"))
      (node (ref "R49") (pin "1") (pintype "passive"))
      (node (ref "R50") (pin "2") (pintype "passive"))
      (node (ref "R52") (pin "1") (pintype "passive"))
      (node (ref "R53") (pin "1") (pintype "passive"))
      (node (ref "R57") (pin "1") (pintype "passive"))
      (node (ref "R6") (pin "2") (pintype "passive"))
      (node (ref "R62") (pin "1") (pintype "passive"))
      (node (ref "R64") (pin "1") (pintype "passive"))
      (node (ref "R8") (pin "2") (pintype "passive"))
      (node (ref "SD_CARD") (pin "3") (pinfunction "VSS_3") (pintype "passive"))
      (node (ref "SD_CARD") (pin "6") (pinfunction "VSS_6") (pintype "passive"))
      (node (ref "U1") (pin "2") (pinfunction "GND_2") (pintype "passive"))
      (node (ref "U10") (pin "5") (pinfunction "GND_5") (pintype "passive"))
      (node (ref "U11") (pin "15") (pinfunction "GND_15") (pintype "passive"))
      (node (ref "U2") (pin "1") (pinfunction "GND_1") (pintype "passive"))
      (node (ref "U3") (pin "6") (pinfunction "GND_6") (pintype "passive"))
      (node (ref "U3") (pin "7") (pinfunction "IN3_7") (pintype "passive"))
      (node (ref "U3") (pin "8") (pinfunction "IN4_8") (pintype "passive"))
      (node (ref "U4") (pin "2") (pinfunction "GND_2") (pintype "passive"))
      (node (ref "U5") (pin "2") (pinfunction "GND_2") (pintype "passive"))
      (node (ref "U6") (pin "1") (pinfunction "GND_1") (pintype "passive"))
      (node (ref "U7") (pin "1") (pinfunction "GND_1") (pintype "passive"))
      (node (ref "U8") (pin "25") (pinfunction "GND_25") (pintype "passive"))
      (node (ref "U9") (pin "2") (pinfunction "GND_2") (pintype "power_in"))
      (node (ref "U9") (pin "8") (pinfunction "RS_8") (pintype "input"))
      (node (ref "USB_232") (pin "5") (pinfunction "GND_5") (pintype "passive"))
    )
    (net (code "209") (name "Net-(BAT-VCC)") (class "Default")
      (node (ref "BAT") (pin "1") (pinfunction "VCC_1") (pintype "passive"))
      (node (ref "D13") (pin "1") (pintype "passive"))
    )
    (net (code "210") (name "Net-(BEEP-G)") (class "Default")
      (node (ref "BEEP") (pin "2") (pinfunction "G_2") (pintype "passive"))
      (node (ref "Q3") (pin "3") (pinfunction "C_3") (pintype "passive"))
    )
    (net (code "211") (name "Net-(C3-Pad2)") (class "Default")
      (node (ref "C3") (pin "2") (pintype "passive"))
      (node (ref "C4") (pin "2") (pintype "passive"))
      (node (ref "J2") (pin "46") (pinfunction "Vcom_46") (pintype "passive"))
      (node (ref "J2") (pin "6") (pinfunction "Vcom_6") (pintype "passive"))
      (node (ref "R10") (pin "1") (pintype "passive"))
      (node (ref "R9") (pin "1") (pintype "passive"))
      (node (ref "VCOM") (pin "1") (pinfunction "1_1") (pintype "passive"))
    )
    (net (code "212") (name "Net-(C12-Pad1)") (class "Default")
      (node (ref "C12") (pin "1") (pintype "passive"))
      (node (ref "D2") (pin "1") (pintype "passive"))
      (node (ref "D4") (pin "1") (pintype "passive"))
    )
    (net (code "213") (name "Net-(C13-Pad1)") (class "Default")
      (node (ref "C13") (pin "1") (pintype "passive"))
      (node (ref "D3") (pin "3") (pintype "passive"))
    )
    (net (code "214") (name "Net-(C14-Pad2)") (class "Default")
      (node (ref "C14") (pin "2") (pintype "passive"))
      (node (ref "D4") (pin "3") (pintype "passive"))
    )
    (net (code "215") (name "Net-(C15-Pad1)") (class "Default")
      (node (ref "C15") (pin "1") (pintype "passive"))
      (node (ref "D3") (pin "2") (pintype "passive"))
      (node (ref "D5") (pin "2") (pintype "passive"))
    )
    (net (code "216") (name "Net-(C18-Pad2)") (class "Default")
      (node (ref "C18") (pin "2") (pintype "passive"))
      (node (ref "C19") (pin "2") (pintype "passive"))
      (node (ref "R22") (pin "1") (pintype "passive"))
      (node (ref "U3") (pin "1") (pinfunction "VCC_1") (pintype "passive"))
    )
    (net (code "217") (name "Net-(D7-Pad1)") (class "Default")
      (node (ref "D7") (pin "1") (pintype "passive"))
      (node (ref "DC_IN") (pin "1") (pintype "passive"))
      (node (ref "PWR1") (pin "1") (pinfunction "1_1") (pintype "passive"))
      (node (ref "PWR_IN") (pin "1") (pinfunction "1_1") (pintype "passive"))
    )
    (net (code "218") (name "Net-(EARTHNET-LED(G)_K)") (class "Default")
      (node (ref "EARTHNET") (pin "10") (pinfunction "LED(G)_K_10") (pintype "passive"))
      (node (ref "R52") (pin "2") (pintype "passive"))
    )
    (net (code "219") (name "Net-(EARTHNET-LED(Y)_K)") (class "Default")
      (node (ref "EARTHNET") (pin "11") (pinfunction "LED(Y)_K_11") (pintype "passive"))
      (node (ref "R53") (pin "2") (pintype "passive"))
    )
    (net (code "220") (name "Net-(J2-MODE)") (class "Default")
      (node (ref "J2") (pin "8") (pinfunction "MODE_8") (pintype "passive"))
      (node (ref "R2") (pin "1") (pintype "passive"))
    )
    (net (code "221") (name "Net-(PWR-Pad1)") (class "Default")
      (node (ref "PWR") (pin "1") (pinfunction "1_1") (pintype "passive"))
      (node (ref "R18") (pin "2") (pintype "passive"))
    )
    (net (code "222") (name "Net-(Q1-B)") (class "Default")
      (node (ref "Q1") (pin "2") (pinfunction "B_2") (pintype "passive"))
      (node (ref "R31") (pin "2") (pintype "passive"))
    )
    (net (code "223") (name "Net-(Q1-C)") (class "Default")
      (node (ref "D11") (pin "2") (pintype "passive"))
      (node (ref "Q1") (pin "3") (pinfunction "C_3") (pintype "passive"))
      (node (ref "R30") (pin "2") (pintype "passive"))
    )
    (net (code "224") (name "Net-(Q1-E)") (class "Default")
      (node (ref "Q1") (pin "1") (pinfunction "E_1") (pintype "passive"))
      (node (ref "R32") (pin "1") (pintype "passive"))
      (node (ref "U7") (pin "14") (pinfunction "RTS#_14") (pintype "passive"))
    )
    (net (code "225") (name "Net-(Q2-B)") (class "Default")
      (node (ref "Q2") (pin "2") (pinfunction "B_2") (pintype "passive"))
      (node (ref "R32") (pin "2") (pintype "passive"))
    )
    (net (code "226") (name "Net-(Q2-C)") (class "Default")
      (node (ref "Q2") (pin "3") (pinfunction "C_3") (pintype "passive"))
      (node (ref "R33") (pin "1") (pintype "passive"))
    )
    (net (code "227") (name "Net-(Q3-B)") (class "Default")
      (node (ref "Q3") (pin "2") (pinfunction "B_2") (pintype "passive"))
      (node (ref "R63") (pin "2") (pintype "passive"))
      (node (ref "R64") (pin "2") (pintype "passive"))
    )
    (net (code "228") (name "Net-(U1-EN)") (class "Default")
      (node (ref "R17") (pin "1") (pintype "passive"))
      (node (ref "U1") (pin "4") (pinfunction "EN_4") (pintype "passive"))
    )
    (net (code "229") (name "Net-(U1-SW)") (class "Default")
      (node (ref "D1") (pin "1") (pintype "passive"))
      (node (ref "L1") (pin "2") (pinfunction "2_2") (pintype "passive"))
      (node (ref "U1") (pin "1") (pinfunction "SW_1") (pintype "passive"))
    )
    (net (code "230") (name "Net-(U4-FB)") (class "Default")
      (node (ref "C24") (pin "2") (pintype "passive"))
      (node (ref "R24") (pin "1") (pintype "passive"))
      (node (ref "R25") (pin "2") (pintype "passive"))
      (node (ref "U4") (pin "3") (pinfunction "FB_3") (pintype "passive"))
    )
    (net (code "231") (name "Net-(U4-SW)") (class "Default")
      (node (ref "C13") (pin "2") (pintype "passive"))
      (node (ref "C14") (pin "1") (pintype "passive"))
      (node (ref "D6") (pin "1") (pintype "passive"))
      (node (ref "L2") (pin "1") (pinfunction "1_1") (pintype "passive"))
      (node (ref "U4") (pin "1") (pinfunction "SW_1") (pintype "passive"))
    )
    (net (code "232") (name "Net-(U5-BST)") (class "Default")
      (node (ref "C25") (pin "1") (pintype "passive"))
      (node (ref "U5") (pin "1") (pinfunction "BST_1") (pintype "passive"))
    )
    (net (code "233") (name "Net-(U5-EN)") (class "Default")
      (node (ref "R27") (pin "2") (pintype "passive"))
      (node (ref "U5") (pin "4") (pinfunction "EN_4") (pintype "passive"))
    )
    (net (code "234") (name "Net-(U5-FB)") (class "Default")
      (node (ref "R26") (pin "1") (pintype "passive"))
      (node (ref "R28") (pin "2") (pintype "passive"))
      (node (ref "U5") (pin "3") (pinfunction "FB_3") (pintype "passive"))
    )
    (net (code "235") (name "Net-(U5-IN)") (class "Default")
      (node (ref "C28") (pin "2") (pintype "passive"))
      (node (ref "C29") (pin "2") (pintype "passive"))
      (node (ref "D7") (pin "2") (pintype "passive"))
      (node (ref "R27") (pin "1") (pintype "passive"))
      (node (ref "U5") (pin "5") (pinfunction "IN_5") (pintype "passive"))
    )
    (net (code "236") (name "Net-(U5-SW)") (class "Default")
      (node (ref "C25") (pin "2") (pintype "passive"))
      (node (ref "D8") (pin "2") (pintype "passive"))
      (node (ref "L3") (pin "2") (pinfunction "2_2") (pintype "passive"))
      (node (ref "U5") (pin "6") (pinfunction "SW_6") (pintype "passive"))
    )
    (net (code "237") (name "Net-(U7-DTR#)") (class "Default")
      (node (ref "R31") (pin "1") (pintype "passive"))
      (node (ref "U7") (pin "13") (pinfunction "DTR#_13") (pintype "passive"))
    )
    (net (code "238") (name "Net-(U7-V3)") (class "Default")
      (node (ref "C35") (pin "2") (pintype "passive"))
      (node (ref "U7") (pin "4") (pinfunction "V3_4") (pintype "passive"))
    )
    (net (code "239") (name "Net-(U7-XI)") (class "Default")
      (node (ref "C38") (pin "2") (pintype "passive"))
      (node (ref "U7") (pin "7") (pinfunction "XI_7") (pintype "passive"))
      (node (ref "Y1") (pin "1") (pinfunction "OSC1_1") (pintype "passive"))
    )
    (net (code "240") (name "Net-(U7-XO)") (class "Default")
      (node (ref "C37") (pin "2") (pintype "passive"))
      (node (ref "U7") (pin "8") (pinfunction "XO_8") (pintype "passive"))
      (node (ref "Y1") (pin "2") (pinfunction "OSC2_2") (pintype "passive"))
    )
    (net (code "241") (name "Net-(U8-MDIO)") (class "Default")
      (node (ref "R43") (pin "1") (pintype "passive"))
      (node (ref "U8") (pin "12") (pinfunction "MDIO_12") (pintype "passive"))
    )
    (net (code "242") (name "Net-(U8-RBIAS)") (class "Default")
      (node (ref "R50") (pin "1") (pintype "passive"))
      (node (ref "U8") (pin "24") (pinfunction "RBIAS_24") (pintype "passive"))
    )
    (net (code "243") (name "Net-(U8-VDDCR)") (class "Default")
      (node (ref "C41") (pin "2") (pintype "passive"))
      (node (ref "C42") (pin "2") (pintype "passive"))
      (node (ref "U8") (pin "6") (pinfunction "VDDCR_6") (pintype "passive"))
    )
    (net (code "244") (name "Net-(U8-XTAL1{slash}CLKIN)") (class "Default")
      (node (ref "C47") (pin "2") (pintype "passive"))
      (node (ref "R51") (pin "1") (pintype "passive"))
      (node (ref "U8") (pin "5") (pinfunction "XTAL1/CLKIN_5") (pintype "passive"))
      (node (ref "Y2") (pin "2") (pinfunction "OSC2_2") (pintype "passive"))
    )
    (net (code "245") (name "Net-(U8-XTAL2)") (class "Default")
      (node (ref "C46") (pin "2") (pintype "passive"))
      (node (ref "R51") (pin "2") (pintype "passive"))
      (node (ref "U8") (pin "4") (pinfunction "XTAL2_4") (pintype "passive"))
      (node (ref "Y2") (pin "1") (pinfunction "OSC1_1") (pintype "passive"))
    )
    (net (code "246") (name "Net-(U9-CANH)") (class "Default")
      (node (ref "CAN") (pin "1") (pinfunction "1_1") (pintype "passive"))
      (node (ref "R54") (pin "1") (pintype "passive"))
      (node (ref "U9") (pin "7") (pinfunction "CANH_7") (pintype "bidirectional"))
    )
    (net (code "247") (name "Net-(U9-CANL)") (class "Default")
      (node (ref "CAN") (pin "2") (pinfunction "2_2") (pintype "passive"))
      (node (ref "R54") (pin "2") (pintype "passive"))
      (node (ref "U9") (pin "6") (pinfunction "CANL_6") (pintype "bidirectional"))
    )
    (net (code "248") (name "Net-(U10-A)") (class "Default")
      (node (ref "R55") (pin "1") (pintype "passive"))
      (node (ref "R56") (pin "2") (pintype "passive"))
      (node (ref "RS485") (pin "1") (pinfunction "1_1") (pintype "passive"))
      (node (ref "U10") (pin "6") (pinfunction "A_6") (pintype "passive"))
    )
    (net (code "249") (name "Net-(U10-B)") (class "Default")
      (node (ref "R56") (pin "1") (pintype "passive"))
      (node (ref "R57") (pin "2") (pintype "passive"))
      (node (ref "RS485") (pin "2") (pinfunction "2_2") (pintype "passive"))
      (node (ref "U10") (pin "7") (pinfunction "B_7") (pintype "passive"))
    )
    (net (code "250") (name "Net-(U11-C1+)") (class "Default")
      (node (ref "C58") (pin "1") (pintype "passive"))
      (node (ref "U11") (pin "1") (pinfunction "C1+_1") (pintype "passive"))
    )
    (net (code "251") (name "Net-(U11-C1-)") (class "Default")
      (node (ref "C58") (pin "2") (pintype "passive"))
      (node (ref "U11") (pin "3") (pinfunction "C1-_3") (pintype "passive"))
    )
    (net (code "252") (name "Net-(U11-C2+)") (class "Default")
      (node (ref "C60") (pin "1") (pintype "passive"))
      (node (ref "U11") (pin "4") (pinfunction "C2+_4") (pintype "passive"))
    )
    (net (code "253") (name "Net-(U11-C2-)") (class "Default")
      (node (ref "C60") (pin "2") (pintype "passive"))
      (node (ref "U11") (pin "5") (pinfunction "C2-_5") (pintype "passive"))
    )
    (net (code "254") (name "Net-(U11-V+)") (class "Default")
      (node (ref "C59") (pin "1") (pintype "passive"))
      (node (ref "U11") (pin "2") (pinfunction "V+_2") (pintype "passive"))
    )
    (net (code "255") (name "Net-(U11-V-)") (class "Default")
      (node (ref "C61") (pin "1") (pintype "passive"))
      (node (ref "U11") (pin "6") (pinfunction "V-_6") (pintype "passive"))
    )
    (net (code "256") (name "VBTN") (class "Default")
      (node (ref "C26") (pin "2") (pintype "passive"))
      (node (ref "C27") (pin "1") (pinfunction "VCC_1") (pintype "passive"))
      (node (ref "F1") (pin "1") (pintype "passive"))
      (node (ref "L3") (pin "1") (pinfunction "1_1") (pintype "passive"))
      (node (ref "R28") (pin "1") (pintype "passive"))
      (node (ref "R29") (pin "1") (pintype "passive"))
    )
    (net (code "257") (name "VCC-7") (class "Default")
      (node (ref "-7V") (pin "1") (pinfunction "1_1") (pintype "passive"))
      (node (ref "C17") (pin "1") (pintype "passive"))
      (node (ref "D2") (pin "2") (pintype "passive"))
      (node (ref "J2") (pin "42") (pinfunction "VGL_42") (pintype "passive"))
    )
    (net (code "258") (name "VCC3.3") (class "Default")
      (node (ref "BEEP") (pin "1") (pinfunction "P_1") (pintype "passive"))
      (node (ref "C30") (pin "2") (pintype "passive"))
      (node (ref "C31") (pin "1") (pinfunction "VCC_1") (pintype "passive"))
      (node (ref "C39") (pin "1") (pintype "passive"))
      (node (ref "C43") (pin "2") (pintype "passive"))
      (node (ref "C48") (pin "2") (pintype "passive"))
      (node (ref "C56") (pin "2") (pintype "passive"))
      (node (ref "C57") (pin "2") (pintype "passive"))
      (node (ref "D10") (pin "2") (pintype "passive"))
      (node (ref "D12") (pin "1") (pintype "passive"))
      (node (ref "JTAG") (pin "1") (pinfunction "VDD_1") (pintype "passive"))
      (node (ref "JTAG") (pin "2") (pinfunction "VDD_2") (pintype "passive"))
      (node (ref "L4") (pin "2") (pintype "passive"))
      (node (ref "Main_3.3V") (pin "1") (pinfunction "1_1") (pintype "passive"))
      (node (ref "Q2") (pin "1") (pinfunction "E_1") (pintype "passive"))
      (node (ref "R30") (pin "1") (pintype "passive"))
      (node (ref "R34") (pin "1") (pintype "passive"))
      (node (ref "R35") (pin "1") (pintype "passive"))
      (node (ref "R36") (pin "1") (pintype "passive"))
      (node (ref "R37") (pin "1") (pintype "passive"))
      (node (ref "R38") (pin "1") (pintype "passive"))
      (node (ref "R39") (pin "2") (pintype "passive"))
      (node (ref "R41") (pin "2") (pintype "passive"))
      (node (ref "R55") (pin "2") (pintype "passive"))
      (node (ref "R58") (pin "1") (pintype "passive"))
      (node (ref "R59") (pin "1") (pintype "passive"))
      (node (ref "R60") (pin "1") (pintype "passive"))
      (node (ref "R61") (pin "1") (pintype "passive"))
      (node (ref "SD_CARD") (pin "4") (pinfunction "VDD_4") (pintype "passive"))
      (node (ref "U10") (pin "8") (pinfunction "VCC_8") (pintype "passive"))
      (node (ref "U11") (pin "16") (pinfunction "VCC_16") (pintype "passive"))
      (node (ref "U6") (pin "2") (pinfunction "OUT_2") (pintype "passive"))
      (node (ref "U6") (pin "4") (pinfunction "OUT_4") (pintype "passive"))
      (node (ref "U8") (pin "9") (pinfunction "VDDIO_9") (pintype "passive"))
    )
    (net (code "259") (name "VCC3.3E") (class "Default")
      (node (ref "C44") (pin "2") (pintype "passive"))
      (node (ref "C45") (pin "2") (pintype "passive"))
      (node (ref "C49") (pin "2") (pintype "passive"))
      (node (ref "C50") (pin "2") (pintype "passive"))
      (node (ref "EARTHNET") (pin "4") (pinfunction "TCT_4") (pintype "passive"))
      (node (ref "EARTHNET") (pin "5") (pinfunction "RCT_5") (pintype "passive"))
      (node (ref "L4") (pin "1") (pintype "passive"))
      (node (ref "R44") (pin "1") (pintype "passive"))
      (node (ref "R45") (pin "1") (pintype "passive"))
      (node (ref "R46") (pin "1") (pintype "passive"))
      (node (ref "R47") (pin "1") (pintype "passive"))
      (node (ref "U8") (pin "1") (pinfunction "VDD2A_1") (pintype "passive"))
      (node (ref "U8") (pin "19") (pinfunction "VDD1A_19") (pintype "passive"))
    )
    (net (code "260") (name "VCC5") (class "Default")
      (node (ref "C32") (pin "2") (pintype "passive"))
      (node (ref "C33") (pin "1") (pintype "passive"))
      (node (ref "C34") (pin "1") (pintype "passive"))
      (node (ref "C36") (pin "1") (pintype "passive"))
      (node (ref "C40") (pin "1") (pintype "passive"))
      (node (ref "C55") (pin "2") (pintype "passive"))
      (node (ref "D9") (pin "2") (pintype "passive"))
      (node (ref "M1") (pin "J1_58") (pinfunction "VCC5_J1_58") (pintype "passive"))
      (node (ref "M1") (pin "J1_59") (pinfunction "VCC5_J1_59") (pintype "passive"))
      (node (ref "M1") (pin "J1_60") (pinfunction "VCC5_J1_60") (pintype "passive"))
      (node (ref "Main_5V") (pin "1") (pinfunction "1_1") (pintype "passive"))
      (node (ref "R29") (pin "2") (pintype "passive"))
      (node (ref "U6") (pin "3") (pinfunction "IN_3") (pintype "passive"))
      (node (ref "U7") (pin "16") (pinfunction "VCC_16") (pintype "passive"))
      (node (ref "U9") (pin "3") (pinfunction "VCC_3") (pintype "power_in"))
    )
    (net (code "261") (name "VCC10.4") (class "Default")
      (node (ref "10.4V") (pin "1") (pinfunction "1_1") (pintype "passive"))
      (node (ref "C15") (pin "2") (pintype "passive"))
      (node (ref "C20") (pin "2") (pintype "passive"))
      (node (ref "C21") (pin "2") (pintype "passive"))
      (node (ref "C24") (pin "1") (pintype "passive"))
      (node (ref "D3") (pin "1") (pintype "passive"))
      (node (ref "D6") (pin "2") (pintype "passive"))
      (node (ref "J2") (pin "43") (pinfunction "AVDD_43") (pintype "passive"))
      (node (ref "R24") (pin "2") (pintype "passive"))
      (node (ref "R9") (pin "2") (pintype "passive"))
    )
    (net (code "262") (name "VCC16") (class "Default")
      (node (ref "16V") (pin "1") (pinfunction "1_1") (pintype "passive"))
      (node (ref "C16") (pin "1") (pintype "passive"))
      (node (ref "D5") (pin "1") (pintype "passive"))
      (node (ref "J2") (pin "41") (pinfunction "VGH_41") (pintype "passive"))
    )
    (net (code "263") (name "VUSB") (class "Default")
      (node (ref "F1") (pin "2") (pintype "passive"))
      (node (ref "USB_232") (pin "1") (pinfunction "VCC_1") (pintype "passive"))
    )
    (net (code "264") (name "unconnected-(EARTHNET-NC-Pad7)") (class "Default")
      (node (ref "EARTHNET") (pin "7") (pinfunction "NC_7") (pintype "passive"))
    )
    (net (code "265") (name "unconnected-(J2-NC-Pad45)") (class "Default")
      (node (ref "J2") (pin "45") (pinfunction "NC_45") (pintype "passive"))
    )
    (net (code "266") (name "unconnected-(J2-NC-Pad49)") (class "Default")
      (node (ref "J2") (pin "49") (pinfunction "NC_49") (pintype "passive"))
    )
    (net (code "267") (name "unconnected-(J2-NC-Pad50)") (class "Default")
      (node (ref "J2") (pin "50") (pinfunction "NC_50") (pintype "passive"))
    )
    (net (code "268") (name "unconnected-(JTAG-NC-Pad11)") (class "Default")
      (node (ref "JTAG") (pin "11") (pinfunction "NC_11") (pintype "passive"))
    )
    (net (code "269") (name "unconnected-(JTAG-NC-Pad17)") (class "Default")
      (node (ref "JTAG") (pin "17") (pinfunction "NC_17") (pintype "passive"))
    )
    (net (code "270") (name "unconnected-(JTAG-NC-Pad19)") (class "Default")
      (node (ref "JTAG") (pin "19") (pinfunction "NC_19") (pintype "passive"))
    )
    (net (code "271") (name "unconnected-(SD_CARD-CD-Pad10)") (class "Default")
      (node (ref "SD_CARD") (pin "10") (pinfunction "CD_10") (pintype "passive"))
    )
    (net (code "272") (name "unconnected-(SD_CARD-GND-Pad11)") (class "Default")
      (node (ref "SD_CARD") (pin "11") (pinfunction "GND_11") (pintype "passive"))
    )
    (net (code "273") (name "unconnected-(SD_CARD-WP-Pad12)") (class "Default")
      (node (ref "SD_CARD") (pin "12") (pinfunction "WP_12") (pintype "passive"))
    )
    (net (code "274") (name "unconnected-(U3-BUSY-Pad13)") (class "Default")
      (node (ref "U3") (pin "13") (pinfunction "BUSY_13") (pintype "passive"))
    )
    (net (code "275") (name "unconnected-(U7-CTS#-Pad9)") (class "Default")
      (node (ref "U7") (pin "9") (pinfunction "CTS#_9") (pintype "passive+no_connect"))
    )
    (net (code "276") (name "unconnected-(U7-DCD#-Pad12)") (class "Default")
      (node (ref "U7") (pin "12") (pinfunction "DCD#_12") (pintype "passive+no_connect"))
    )
    (net (code "277") (name "unconnected-(U7-DSR#-Pad10)") (class "Default")
      (node (ref "U7") (pin "10") (pinfunction "DSR#_10") (pintype "passive+no_connect"))
    )
    (net (code "278") (name "unconnected-(U7-R232-Pad15)") (class "Default")
      (node (ref "U7") (pin "15") (pinfunction "R232_15") (pintype "passive+no_connect"))
    )
    (net (code "279") (name "unconnected-(U7-RI#-Pad11)") (class "Default")
      (node (ref "U7") (pin "11") (pinfunction "RI#_11") (pintype "passive+no_connect"))
    )
    (net (code "280") (name "unconnected-(U8-RXER{slash}PHYAD0-Pad10)") (class "Default")
      (node (ref "U8") (pin "10") (pinfunction "RXER/PHYAD0_10") (pintype "passive"))
    )
    (net (code "281") (name "unconnected-(U9-Vref-Pad5)") (class "Default")
      (node (ref "U9") (pin "5") (pinfunction "Vref_5") (pintype "output"))
    )
    (net (code "282") (name "unconnected-(U11-DIN1-Pad11)") (class "Default")
      (node (ref "U11") (pin "11") (pinfunction "DIN1_11") (pintype "passive"))
    )
    (net (code "283") (name "unconnected-(U11-DOUT1-Pad14)") (class "Default")
      (node (ref "U11") (pin "14") (pinfunction "DOUT1_14") (pintype "passive"))
    )
    (net (code "284") (name "unconnected-(U11-RIN1-Pad13)") (class "Default")
      (node (ref "U11") (pin "13") (pinfunction "RIN1_13") (pintype "passive"))
    )
    (net (code "285") (name "unconnected-(U11-ROUT1-Pad12)") (class "Default")
      (node (ref "U11") (pin "12") (pinfunction "ROUT1_12") (pintype "passive"))
    )
    (net (code "286") (name "unconnected-(USB_232-NC-Pad4)") (class "Default")
      (node (ref "USB_232") (pin "4") (pinfunction "NC_4") (pintype "passive"))
    )
  )
)
